# Cosmic_Pi_V2.net
KiCad netlist of a schematic drawn in EAGLE
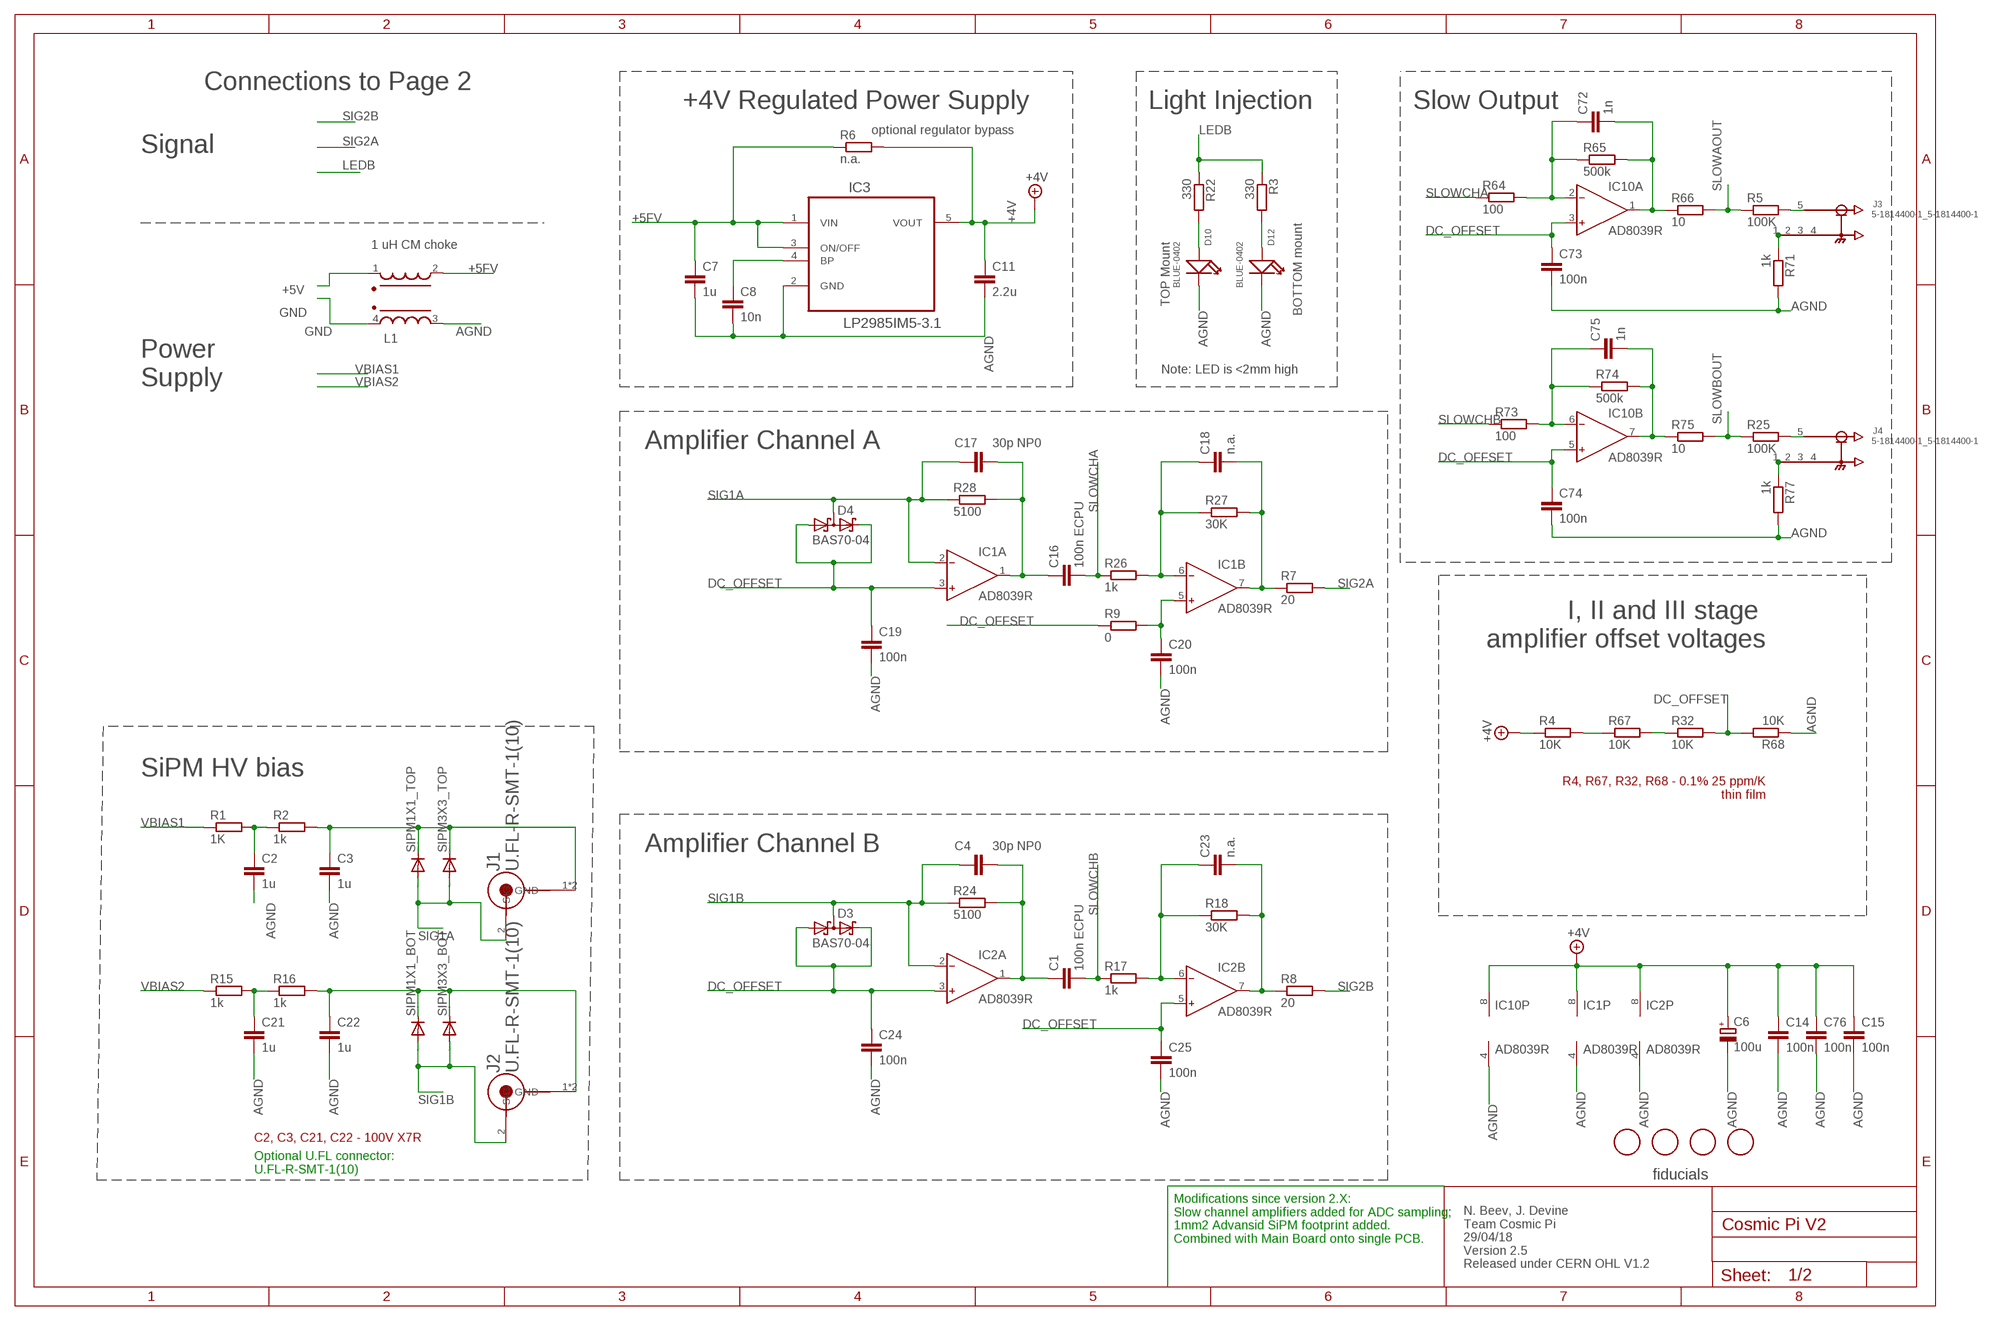
[diagram p0: schematic, sheet 1]
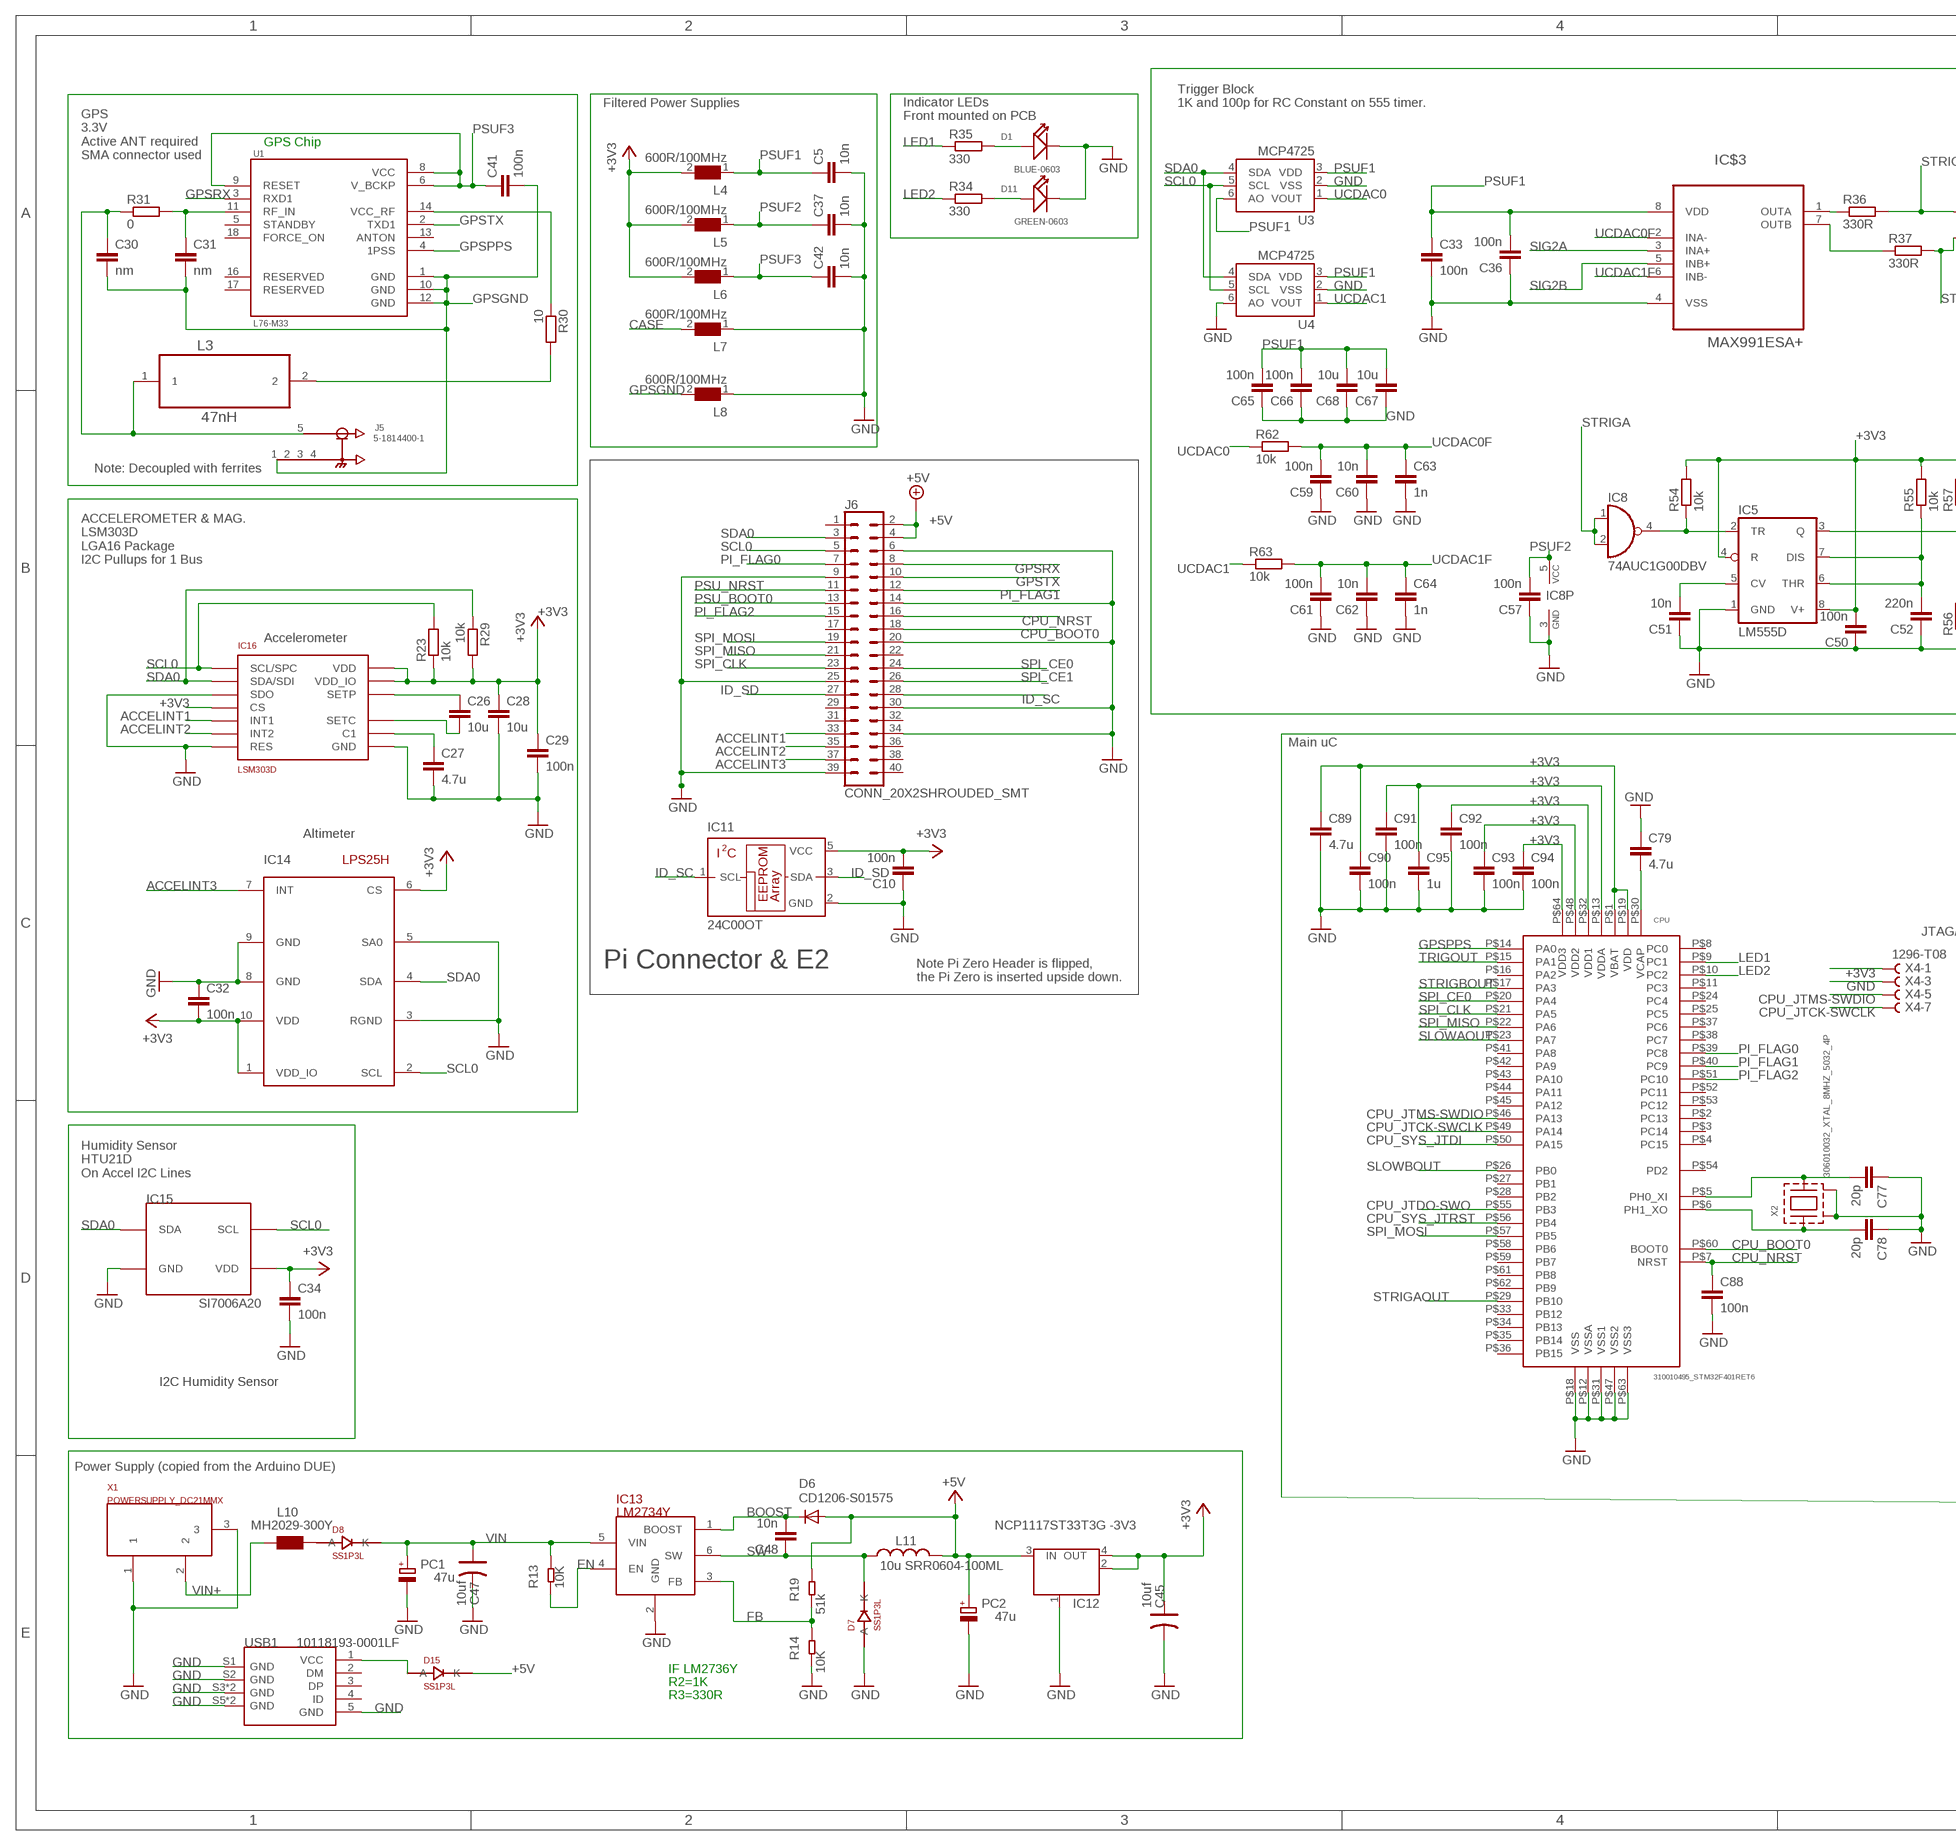
[diagram p1: schematic, sheet 2, part 1 of 2]
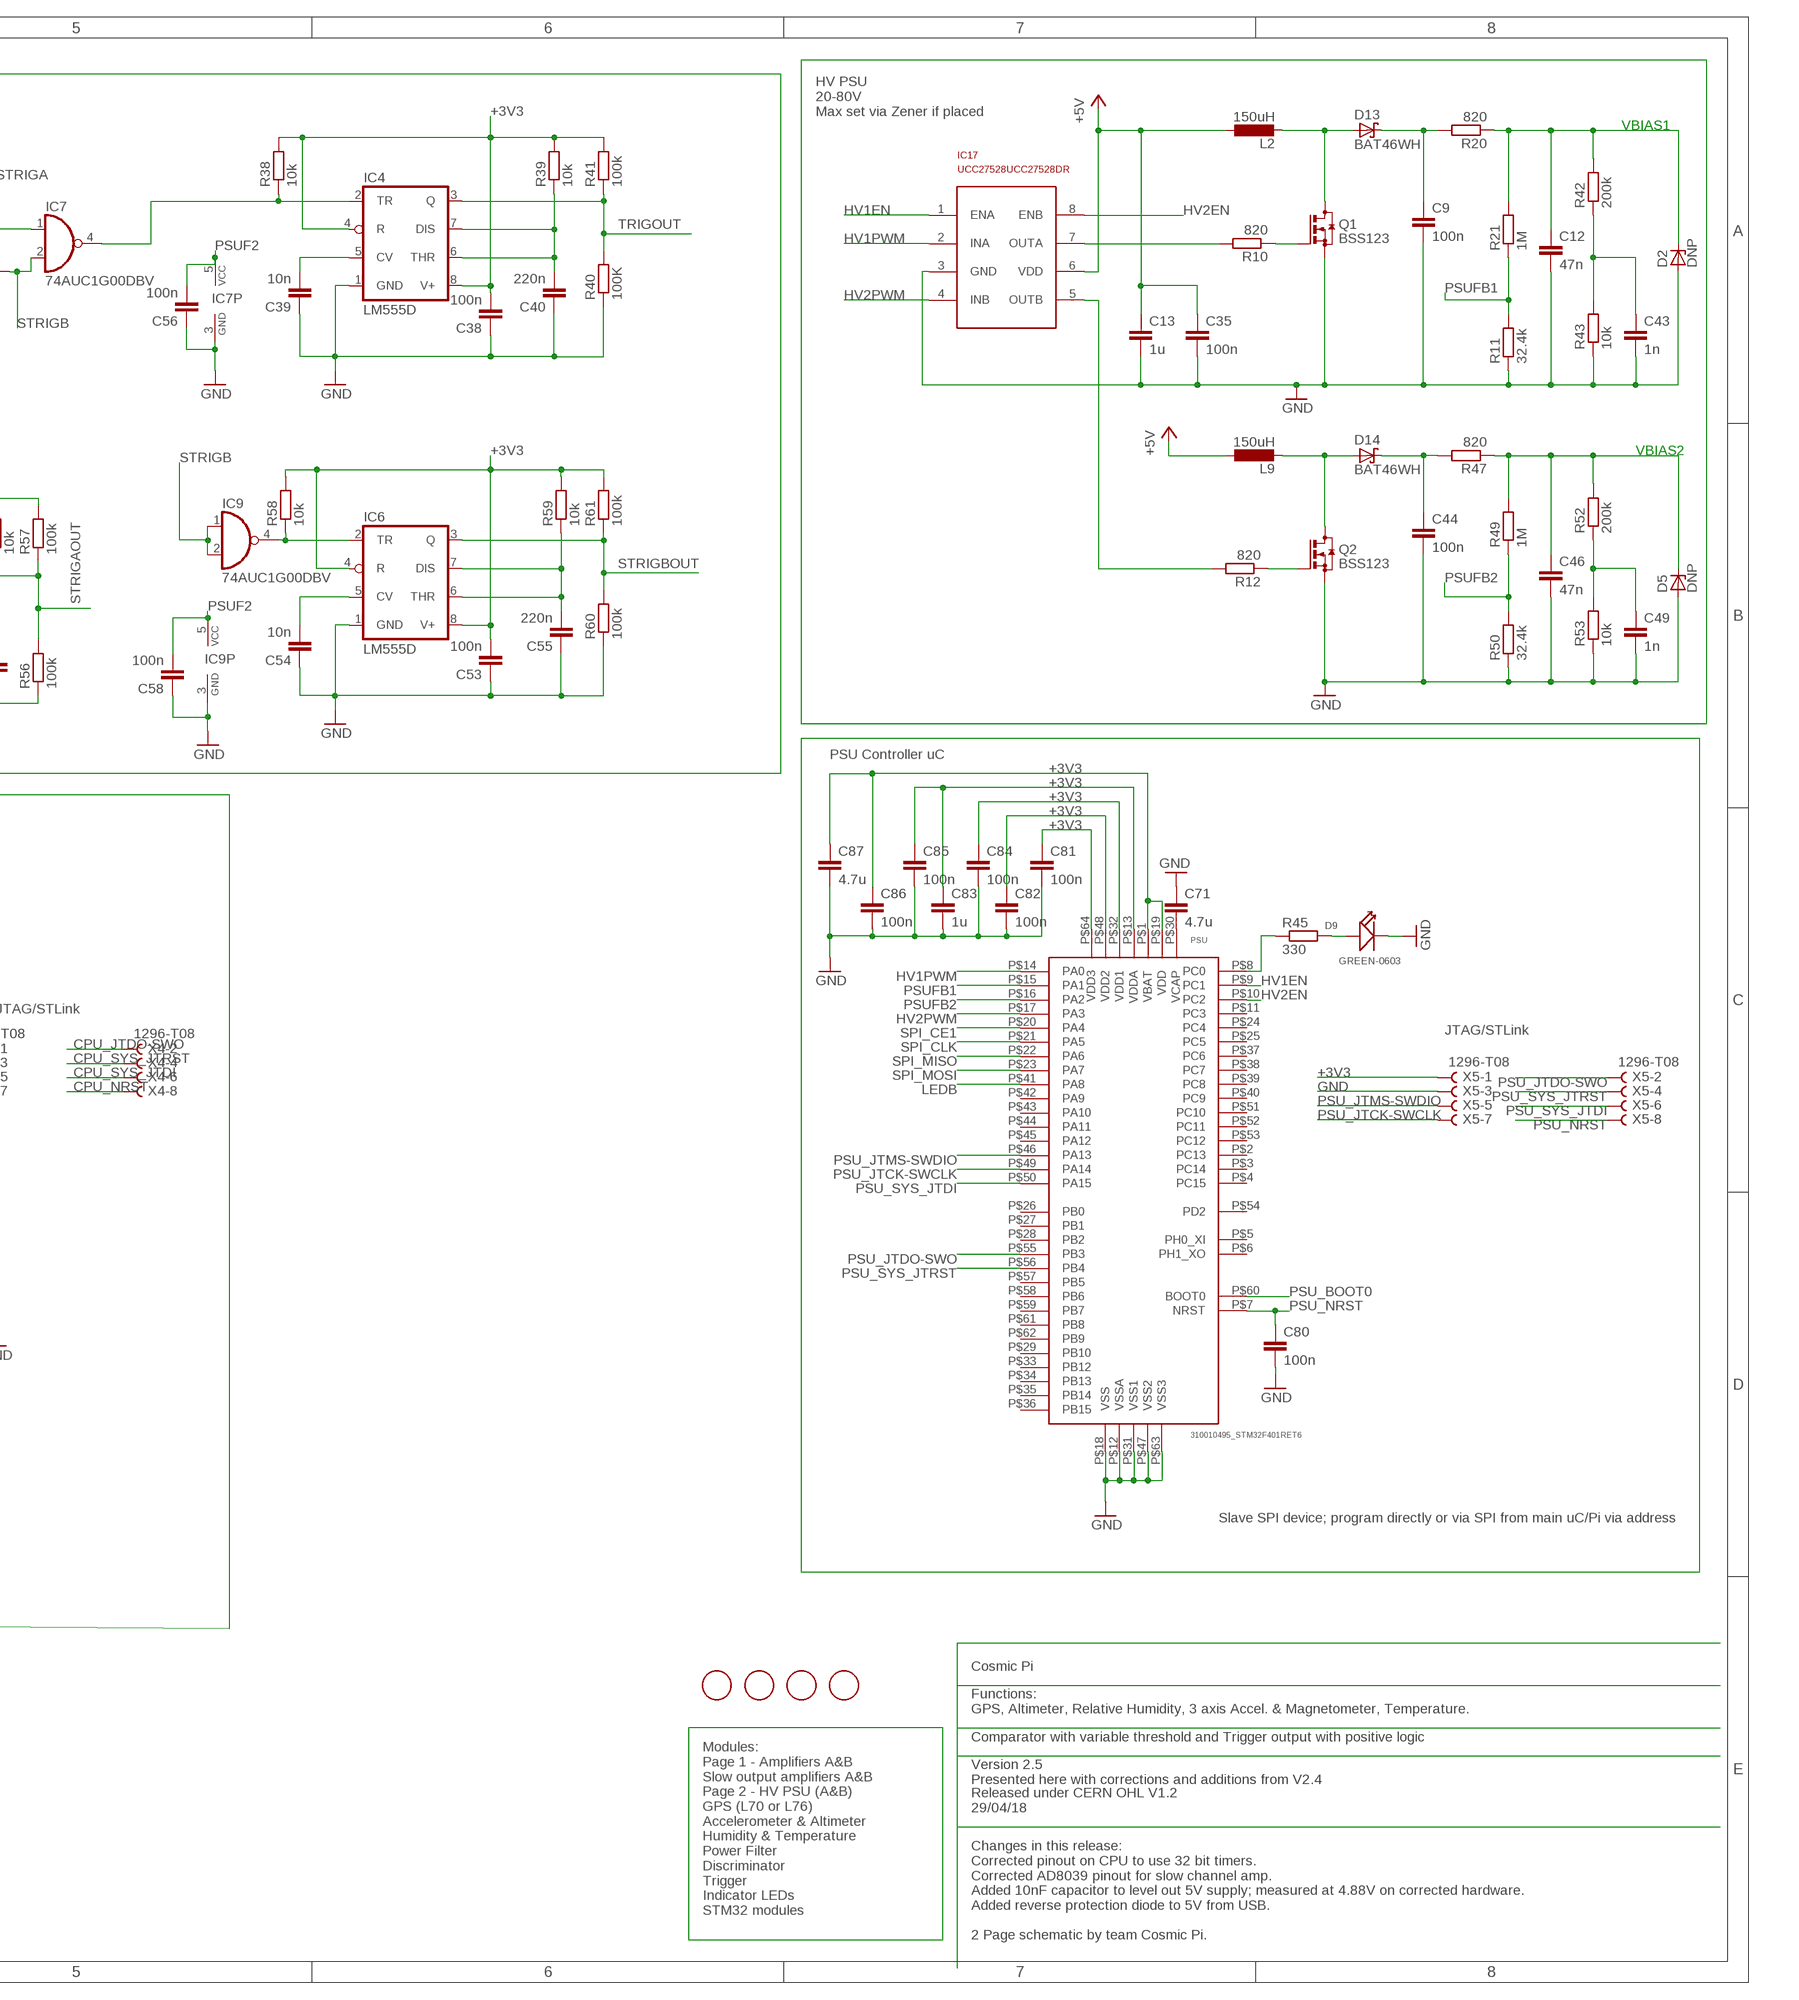
[diagram p2: schematic, sheet 2, part 2 of 2]

(export (version "E")
  (design (tool "Eeschema 10.0.6"))
  (components
    (comp (ref "C5")
      (value "10n")
      (footprint "eagle-import:C0603")
      (libsource (lib "eagle-import") (part "resistor_348_C-EUC0603"))
    )
    (comp (ref "C9")
      (value "100n")
      (footprint "eagle-import:C0603")
      (libsource (lib "eagle-import") (part "rcl_334_C-EUC0603"))
    )
    (comp (ref "C10")
      (value "100n")
      (footprint "eagle-import:C0603")
      (libsource (lib "eagle-import") (part "resistor_348_C-EUC0603"))
    )
    (comp (ref "C12")
      (value "47n")
      (footprint "eagle-import:C0603")
      (libsource (lib "eagle-import") (part "rcl_334_C-EUC0603"))
    )
    (comp (ref "C13")
      (value "1u")
      (footprint "eagle-import:C0603")
      (libsource (lib "eagle-import") (part "resistor_348_C-EUC0603"))
    )
    (comp (ref "C26")
      (value "10u")
      (footprint "eagle-import:C0603")
      (libsource (lib "eagle-import") (part "resistor_348_C-EUC0603"))
    )
    (comp (ref "C27")
      (value "4.7u")
      (footprint "eagle-import:C0603")
      (libsource (lib "eagle-import") (part "resistor_348_C-EUC0603"))
    )
    (comp (ref "C28")
      (value "10u")
      (footprint "eagle-import:C0603")
      (libsource (lib "eagle-import") (part "resistor_348_C-EUC0603"))
    )
    (comp (ref "C29")
      (value "100n")
      (footprint "eagle-import:C0603")
      (libsource (lib "eagle-import") (part "resistor_348_C-EUC0603"))
    )
    (comp (ref "C30")
      (value "nm")
      (footprint "eagle-import:C0603")
      (libsource (lib "eagle-import") (part "resistor_348_C-EUC0603"))
    )
    (comp (ref "C31")
      (value "nm")
      (footprint "eagle-import:C0603")
      (libsource (lib "eagle-import") (part "resistor_348_C-EUC0603"))
    )
    (comp (ref "C32")
      (value "100n")
      (footprint "eagle-import:C0603")
      (libsource (lib "eagle-import") (part "resistor_348_C-EUC0603"))
    )
    (comp (ref "C33")
      (value "100n")
      (footprint "eagle-import:C0603")
      (libsource (lib "eagle-import") (part "resistor_348_C-EUC0603"))
    )
    (comp (ref "C34")
      (value "100n")
      (footprint "eagle-import:C0603")
      (libsource (lib "eagle-import") (part "resistor_348_C-EUC0603"))
    )
    (comp (ref "C35")
      (value "100n")
      (footprint "eagle-import:C0603")
      (libsource (lib "eagle-import") (part "resistor_348_C-EUC0603"))
    )
    (comp (ref "C36")
      (value "100n")
      (footprint "eagle-import:C0603")
      (libsource (lib "eagle-import") (part "resistor_348_C-EUC0603"))
    )
    (comp (ref "C37")
      (value "10n")
      (footprint "eagle-import:C0603")
      (libsource (lib "eagle-import") (part "resistor_348_C-EUC0603"))
    )
    (comp (ref "C38")
      (value "100n")
      (footprint "eagle-import:C0603")
      (libsource (lib "eagle-import") (part "resistor_348_C-EUC0603"))
    )
    (comp (ref "C39")
      (value "10n")
      (footprint "eagle-import:C0603")
      (libsource (lib "eagle-import") (part "resistor_348_C-EUC0603"))
    )
    (comp (ref "C40")
      (value "220n")
      (footprint "eagle-import:C0603")
      (libsource (lib "eagle-import") (part "resistor_348_C-EUC0603"))
    )
    (comp (ref "C41")
      (value "100n")
      (footprint "eagle-import:C0603")
      (libsource (lib "eagle-import") (part "resistor_348_C-EUC0603"))
    )
    (comp (ref "C42")
      (value "10n")
      (footprint "eagle-import:C0603")
      (libsource (lib "eagle-import") (part "resistor_348_C-EUC0603"))
    )
    (comp (ref "C43")
      (value "1n")
      (footprint "eagle-import:C0603")
      (libsource (lib "eagle-import") (part "rcl_334_C-EUC0603"))
    )
    (comp (ref "C44")
      (value "100n")
      (footprint "eagle-import:C0603")
      (libsource (lib "eagle-import") (part "rcl_334_C-EUC0603"))
    )
    (comp (ref "C45")
      (value "10uf")
      (footprint "eagle-import:AVX-A")
      (fields (field (name "MPN") "TAJA106K016RNJ"))
      (libsource (lib "eagle-import") (part "TANTALUM-SMD-10UF-16V-10%(AVX-A)"))
    )
    (comp (ref "C46")
      (value "47n")
      (footprint "eagle-import:C0603")
      (libsource (lib "eagle-import") (part "rcl_334_C-EUC0603"))
    )
    (comp (ref "C47")
      (value "10uf")
      (footprint "eagle-import:AVX-A")
      (fields (field (name "MPN") "TAJA106K016RNJ"))
      (libsource (lib "eagle-import") (part "TANTALUM-SMD-10UF-16V-10%(AVX-A)"))
    )
    (comp (ref "C48")
      (value "10n")
      (footprint "eagle-import:C0603")
      (libsource (lib "eagle-import") (part "resistor_348_C-EUC0603"))
    )
    (comp (ref "C49")
      (value "1n")
      (footprint "eagle-import:C0603")
      (libsource (lib "eagle-import") (part "rcl_334_C-EUC0603"))
    )
    (comp (ref "C50")
      (value "100n")
      (footprint "eagle-import:C0603")
      (libsource (lib "eagle-import") (part "resistor_348_C-EUC0603"))
    )
    (comp (ref "C51")
      (value "10n")
      (footprint "eagle-import:C0603")
      (libsource (lib "eagle-import") (part "resistor_348_C-EUC0603"))
    )
    (comp (ref "C52")
      (value "220n")
      (footprint "eagle-import:C0603")
      (libsource (lib "eagle-import") (part "resistor_348_C-EUC0603"))
    )
    (comp (ref "C53")
      (value "100n")
      (footprint "eagle-import:C0603")
      (libsource (lib "eagle-import") (part "resistor_348_C-EUC0603"))
    )
    (comp (ref "C54")
      (value "10n")
      (footprint "eagle-import:C0603")
      (libsource (lib "eagle-import") (part "resistor_348_C-EUC0603"))
    )
    (comp (ref "C55")
      (value "220n")
      (footprint "eagle-import:C0603")
      (libsource (lib "eagle-import") (part "resistor_348_C-EUC0603"))
    )
    (comp (ref "C56")
      (value "100n")
      (footprint "eagle-import:C0603")
      (libsource (lib "eagle-import") (part "resistor_348_C-EUC0603"))
    )
    (comp (ref "C57")
      (value "100n")
      (footprint "eagle-import:C0603")
      (libsource (lib "eagle-import") (part "resistor_348_C-EUC0603"))
    )
    (comp (ref "C58")
      (value "100n")
      (footprint "eagle-import:C0603")
      (libsource (lib "eagle-import") (part "resistor_348_C-EUC0603"))
    )
    (comp (ref "C59")
      (value "100n")
      (footprint "eagle-import:C0603")
      (libsource (lib "eagle-import") (part "resistor_348_C-EUC0603"))
    )
    (comp (ref "C60")
      (value "10n")
      (footprint "eagle-import:C0603")
      (libsource (lib "eagle-import") (part "resistor_348_C-EUC0603"))
    )
    (comp (ref "C61")
      (value "100n")
      (footprint "eagle-import:C0603")
      (libsource (lib "eagle-import") (part "resistor_348_C-EUC0603"))
    )
    (comp (ref "C62")
      (value "10n")
      (footprint "eagle-import:C0603")
      (libsource (lib "eagle-import") (part "resistor_348_C-EUC0603"))
    )
    (comp (ref "C63")
      (value "1n")
      (footprint "eagle-import:C0603")
      (libsource (lib "eagle-import") (part "rcl_334_C-EUC0603"))
    )
    (comp (ref "C64")
      (value "1n")
      (footprint "eagle-import:C0603")
      (libsource (lib "eagle-import") (part "rcl_334_C-EUC0603"))
    )
    (comp (ref "C65")
      (value "100n")
      (footprint "eagle-import:C0603")
      (libsource (lib "eagle-import") (part "resistor_348_C-EUC0603"))
    )
    (comp (ref "C66")
      (value "100n")
      (footprint "eagle-import:C0603")
      (libsource (lib "eagle-import") (part "resistor_348_C-EUC0603"))
    )
    (comp (ref "C67")
      (value "10u")
      (footprint "eagle-import:C0603")
      (libsource (lib "eagle-import") (part "resistor_348_C-EUC0603"))
    )
    (comp (ref "C68")
      (value "10u")
      (footprint "eagle-import:C0603")
      (libsource (lib "eagle-import") (part "resistor_348_C-EUC0603"))
    )
    (comp (ref "C71")
      (value "4.7u")
      (footprint "eagle-import:C0603")
      (libsource (lib "eagle-import") (part "resistor_348_C-EUC0603"))
    )
    (comp (ref "C77")
      (value "20p")
      (footprint "eagle-import:C0603")
      (libsource (lib "eagle-import") (part "rcl_334_C-EUC0603"))
    )
    (comp (ref "C78")
      (value "20p")
      (footprint "eagle-import:C0603")
      (libsource (lib "eagle-import") (part "rcl_334_C-EUC0603"))
    )
    (comp (ref "C79")
      (value "4.7u")
      (footprint "eagle-import:C0603")
      (libsource (lib "eagle-import") (part "resistor_348_C-EUC0603"))
    )
    (comp (ref "C80")
      (value "100n")
      (footprint "eagle-import:C0603")
      (libsource (lib "eagle-import") (part "resistor_348_C-EUC0603"))
    )
    (comp (ref "C81")
      (value "100n")
      (footprint "eagle-import:C0603")
      (libsource (lib "eagle-import") (part "resistor_348_C-EUC0603"))
    )
    (comp (ref "C82")
      (value "100n")
      (footprint "eagle-import:C0603")
      (libsource (lib "eagle-import") (part "resistor_348_C-EUC0603"))
    )
    (comp (ref "C83")
      (value "1u")
      (footprint "eagle-import:C0603")
      (libsource (lib "eagle-import") (part "resistor_348_C-EUC0603"))
    )
    (comp (ref "C84")
      (value "100n")
      (footprint "eagle-import:C0603")
      (libsource (lib "eagle-import") (part "resistor_348_C-EUC0603"))
    )
    (comp (ref "C85")
      (value "100n")
      (footprint "eagle-import:C0603")
      (libsource (lib "eagle-import") (part "resistor_348_C-EUC0603"))
    )
    (comp (ref "C86")
      (value "100n")
      (footprint "eagle-import:C0603")
      (libsource (lib "eagle-import") (part "resistor_348_C-EUC0603"))
    )
    (comp (ref "C87")
      (value "4.7u")
      (footprint "eagle-import:C0603")
      (libsource (lib "eagle-import") (part "resistor_348_C-EUC0603"))
    )
    (comp (ref "C88")
      (value "100n")
      (footprint "eagle-import:C0603")
      (libsource (lib "eagle-import") (part "resistor_348_C-EUC0603"))
    )
    (comp (ref "C89")
      (value "4.7u")
      (footprint "eagle-import:C0603")
      (libsource (lib "eagle-import") (part "resistor_348_C-EUC0603"))
    )
    (comp (ref "C90")
      (value "100n")
      (footprint "eagle-import:C0603")
      (libsource (lib "eagle-import") (part "resistor_348_C-EUC0603"))
    )
    (comp (ref "C91")
      (value "100n")
      (footprint "eagle-import:C0603")
      (libsource (lib "eagle-import") (part "resistor_348_C-EUC0603"))
    )
    (comp (ref "C92")
      (value "100n")
      (footprint "eagle-import:C0603")
      (libsource (lib "eagle-import") (part "resistor_348_C-EUC0603"))
    )
    (comp (ref "C93")
      (value "100n")
      (footprint "eagle-import:C0603")
      (libsource (lib "eagle-import") (part "resistor_348_C-EUC0603"))
    )
    (comp (ref "C94")
      (value "100n")
      (footprint "eagle-import:C0603")
      (libsource (lib "eagle-import") (part "resistor_348_C-EUC0603"))
    )
    (comp (ref "C95")
      (value "1u")
      (footprint "eagle-import:C0603")
      (libsource (lib "eagle-import") (part "resistor_348_C-EUC0603"))
    )
    (comp (ref "CPU")
      (value "310010495_STM32F401RET6")
      (footprint "eagle-import:LQFP64")
      (libsource (lib "eagle-import") (part "310010495_STM32F401RET6"))
    )
    (comp (ref "D1")
      (value "BLUE-0603")
      (footprint "eagle-import:LED-0603")
      (fields (field (name "MPN") "19-217-BHC-ZL1M2RY-3T"))
      (libsource (lib "eagle-import") (part "SMD-LED-CLEAR-BLUE(0603)"))
    )
    (comp (ref "D2")
      (value "DNP")
      (footprint "eagle-import:SOT23")
      (libsource (lib "eagle-import") (part "ZENER-DIODESOT23"))
    )
    (comp (ref "D5")
      (value "DNP")
      (footprint "eagle-import:SOT23")
      (libsource (lib "eagle-import") (part "ZENER-DIODESOT23"))
    )
    (comp (ref "D6")
      (value "CD1206-S01575")
      (footprint "eagle-import:MINIMELF")
      (libsource (lib "eagle-import") (part "DIODE-MINIMELF"))
    )
    (comp (ref "D7")
      (value "SS1P3L")
      (footprint "eagle-import:DO220AAL")
      (libsource (lib "eagle-import") (part "SS1P3L"))
    )
    (comp (ref "D8")
      (value "SS1P3L")
      (footprint "eagle-import:DO220AAL")
      (libsource (lib "eagle-import") (part "SS1P3L"))
    )
    (comp (ref "D9")
      (value "GREEN-0603")
      (footprint "eagle-import:LED-0603")
      (fields (field (name "MPN") "19-217-G7C-AN1P2-3T"))
      (libsource (lib "eagle-import") (part "SMD-LED-CLEAR-GREEN(0603)"))
    )
    (comp (ref "D11")
      (value "GREEN-0603")
      (footprint "eagle-import:LED-0603")
      (fields (field (name "MPN") "19-217-G7C-AN1P2-3T"))
      (libsource (lib "eagle-import") (part "SMD-LED-CLEAR-GREEN(0603)"))
    )
    (comp (ref "D13")
      (value "BAT46WH")
      (footprint "eagle-import:SOD123F")
      (libsource (lib "eagle-import") (part "BAT46WH"))
    )
    (comp (ref "D14")
      (value "BAT46WH")
      (footprint "eagle-import:SOD123F")
      (libsource (lib "eagle-import") (part "BAT46WH"))
    )
    (comp (ref "D15")
      (value "SS1P3L")
      (footprint "eagle-import:DO220AAL")
      (libsource (lib "eagle-import") (part "SS1P3L"))
    )
    (comp (ref "IC$3")
      (value "MAX991ESA+")
      (footprint "eagle-import:SOIC-8")
      (libsource (lib "eagle-import") (part "MAX991ESA+"))
    )
    (comp (ref "IC4")
      (value "LM555D")
      (footprint "eagle-import:SO08")
      (libsource (lib "eagle-import") (part "555DLM"))
    )
    (comp (ref "IC5")
      (value "LM555D")
      (footprint "eagle-import:SO08")
      (libsource (lib "eagle-import") (part "555DLM"))
    )
    (comp (ref "IC6")
      (value "LM555D")
      (footprint "eagle-import:SO08")
      (libsource (lib "eagle-import") (part "555DLM"))
    )
    (comp (ref "IC7")
      (value "74AUC1G00DBV")
      (footprint "eagle-import:SOT23-5")
      (libsource (lib "eagle-import") (part "741G00DBVAUC"))
    )
    (comp (ref "IC8")
      (value "74AUC1G00DBV")
      (footprint "eagle-import:SOT23-5")
      (libsource (lib "eagle-import") (part "741G00DBVAUC"))
    )
    (comp (ref "IC9")
      (value "74AUC1G00DBV")
      (footprint "eagle-import:SOT23-5")
      (libsource (lib "eagle-import") (part "741G00DBVAUC"))
    )
    (comp (ref "IC11")
      (value "24C00OT")
      (footprint "eagle-import:SOT23-5L")
      (fields (field (name "MF") "MICROCHIP") (field (name "MPN") "24C00T-I/OT"))
      (libsource (lib "eagle-import") (part "24C0OT0"))
    )
    (comp (ref "IC12")
      (value "NCP1117ST33T3G -3V3")
      (footprint "eagle-import:SOT223")
      (libsource (lib "eagle-import") (part "MC33269ST-3.3T3"))
    )
    (comp (ref "IC13")
      (value "LM2734Y")
      (footprint "eagle-import:SOT23-6")
      (libsource (lib "eagle-import") (part "LM2736Y"))
    )
    (comp (ref "IC14")
      (value "LPS25H")
      (footprint "eagle-import:LPS25H")
      (libsource (lib "eagle-import") (part "LPS25H"))
    )
    (comp (ref "IC15")
      (value "SI7006A20")
      (footprint "eagle-import:3X3DFN")
      (libsource (lib "eagle-import") (part "SI7006A20"))
    )
    (comp (ref "IC16")
      (value "LSM303D")
      (footprint "eagle-import:LGA16L")
      (libsource (lib "eagle-import") (part "LSM303D"))
    )
    (comp (ref "IC17")
      (value "UCC27528UCC27528DR")
      (footprint "eagle-import:ANALOG-DEVICES_SO8")
      (libsource (lib "eagle-import") (part "UCC27528UCC27528DR"))
    )
    (comp (ref "J5")
      (value "5-1814400-1")
      (footprint "eagle-import:TE_5-1814400-1")
      (libsource (lib "eagle-import") (part "5-1814400-1_5-1814400-1"))
    )
    (comp (ref "J6")
      (value "CONN_20X2SHROUDED_SMT")
      (footprint "eagle-import:2X20_SHROUDED_SMT")
      (libsource (lib "eagle-import") (part "CONN_20X2SHROUDED_SMT"))
    )
    (comp (ref "L2")
      (value "150uH")
      (footprint "eagle-import:L1812")
      (libsource (lib "eagle-import") (part "L-EUL1812"))
    )
    (comp (ref "L3")
      (value "47nH")
      (footprint "eagle-import:INDC1608X90N")
      (libsource (lib "eagle-import") (part "B82496C3470J"))
    )
    (comp (ref "L4")
      (value "600R/100MHz")
      (footprint "eagle-import:1206")
      (fields (field (name "MPN") "74279218"))
      (libsource (lib "eagle-import") (part "WE-CBF_1206-74279218"))
    )
    (comp (ref "L5")
      (value "600R/100MHz")
      (footprint "eagle-import:1206")
      (fields (field (name "MPN") "74279218"))
      (libsource (lib "eagle-import") (part "WE-CBF_1206-74279218"))
    )
    (comp (ref "L6")
      (value "600R/100MHz")
      (footprint "eagle-import:1206")
      (fields (field (name "MPN") "74279218"))
      (libsource (lib "eagle-import") (part "WE-CBF_1206-74279218"))
    )
    (comp (ref "L7")
      (value "600R/100MHz")
      (footprint "eagle-import:1206")
      (fields (field (name "MPN") "74279218"))
      (libsource (lib "eagle-import") (part "WE-CBF_1206-74279218"))
    )
    (comp (ref "L8")
      (value "600R/100MHz")
      (footprint "eagle-import:1206")
      (fields (field (name "MPN") "74279218"))
      (libsource (lib "eagle-import") (part "WE-CBF_1206-74279218"))
    )
    (comp (ref "L9")
      (value "150uH")
      (footprint "eagle-import:L1812")
      (libsource (lib "eagle-import") (part "L-EUL1812"))
    )
    (comp (ref "L10")
      (value "MH2029-300Y")
      (footprint "eagle-import:0805")
      (libsource (lib "eagle-import") (part "wuerth-elektronik_WE-CBF_0805"))
    )
    (comp (ref "L11")
      (value "10u SRR0604-100ML")
      (footprint "eagle-import:SRR0604")
      (libsource (lib "eagle-import") (part "L-USSRR0604"))
    )
    (comp (ref "PC1")
      (value "47u")
      (footprint "eagle-import:PANASONIC_D")
      (libsource (lib "eagle-import") (part "CPOL-EUD"))
    )
    (comp (ref "PC2")
      (value "47u")
      (footprint "eagle-import:PANASONIC_D")
      (libsource (lib "eagle-import") (part "CPOL-EUD"))
    )
    (comp (ref "PSU")
      (value "310010495_STM32F401RET6")
      (footprint "eagle-import:LQFP64")
      (libsource (lib "eagle-import") (part "310010495_STM32F401RET6"))
    )
    (comp (ref "Q1")
      (value "BSS123")
      (footprint "eagle-import:SOT23")
      (libsource (lib "eagle-import") (part "BSS123"))
    )
    (comp (ref "Q2")
      (value "BSS123")
      (footprint "eagle-import:SOT23")
      (libsource (lib "eagle-import") (part "BSS123"))
    )
    (comp (ref "R10")
      (value "820")
      (footprint "eagle-import:R0603")
      (libsource (lib "eagle-import") (part "resistor_348_R-EU_R0603"))
    )
    (comp (ref "R11")
      (value "32.4k")
      (footprint "eagle-import:R0603")
      (libsource (lib "eagle-import") (part "resistor_348_R-EU_R0603"))
    )
    (comp (ref "R12")
      (value "820")
      (footprint "eagle-import:R0603")
      (libsource (lib "eagle-import") (part "resistor_348_R-EU_R0603"))
    )
    (comp (ref "R13")
      (value "10K")
      (footprint "eagle-import:R0603")
      (fields (field (name "MPN") "RC0603FR-0710KL"))
      (libsource (lib "eagle-import") (part "SMD-RES-10K-1%-1/10W(0603)"))
    )
    (comp (ref "R14")
      (value "10K")
      (footprint "eagle-import:R0603")
      (fields (field (name "MPN") "RC0603FR-0710KL"))
      (libsource (lib "eagle-import") (part "SMD-RES-10K-1%-1/10W(0603)"))
    )
    (comp (ref "R19")
      (value "51k")
      (footprint "eagle-import:R0603")
      (fields (field (name "MPN") "RC0603JR-0751KL"))
      (libsource (lib "eagle-import") (part "SMD-RES-51K-5%-1/10W(0603)"))
    )
    (comp (ref "R20")
      (value "820")
      (footprint "eagle-import:R0603")
      (libsource (lib "eagle-import") (part "resistor_348_R-EU_R0603"))
    )
    (comp (ref "R21")
      (value "1M")
      (footprint "eagle-import:R0603")
      (libsource (lib "eagle-import") (part "resistor_348_R-EU_R0603"))
    )
    (comp (ref "R23")
      (value "10k")
      (footprint "eagle-import:R0603")
      (libsource (lib "eagle-import") (part "resistor_348_R-EU_R0603"))
    )
    (comp (ref "R29")
      (value "10k")
      (footprint "eagle-import:R0603")
      (libsource (lib "eagle-import") (part "resistor_348_R-EU_R0603"))
    )
    (comp (ref "R30")
      (value "10")
      (footprint "eagle-import:R0603")
      (libsource (lib "eagle-import") (part "resistor_348_R-EU_R0603"))
    )
    (comp (ref "R31")
      (value "0")
      (footprint "eagle-import:R0603")
      (libsource (lib "eagle-import") (part "resistor_348_R-EU_R0603"))
    )
    (comp (ref "R34")
      (value "330")
      (footprint "eagle-import:R0603")
      (libsource (lib "eagle-import") (part "resistor_348_R-EU_R0603"))
    )
    (comp (ref "R35")
      (value "330")
      (footprint "eagle-import:R0603")
      (libsource (lib "eagle-import") (part "resistor_348_R-EU_R0603"))
    )
    (comp (ref "R36")
      (value "330R")
      (footprint "eagle-import:R0603")
      (libsource (lib "eagle-import") (part "resistor_348_R-EU_R0603"))
    )
    (comp (ref "R37")
      (value "330R")
      (footprint "eagle-import:R0603")
      (libsource (lib "eagle-import") (part "resistor_348_R-EU_R0603"))
    )
    (comp (ref "R38")
      (value "10k")
      (footprint "eagle-import:R0603")
      (libsource (lib "eagle-import") (part "resistor_348_R-EU_R0603"))
    )
    (comp (ref "R39")
      (value "10k")
      (footprint "eagle-import:R0603")
      (libsource (lib "eagle-import") (part "resistor_348_R-EU_R0603"))
    )
    (comp (ref "R40")
      (value "100K")
      (footprint "eagle-import:R0603")
      (libsource (lib "eagle-import") (part "resistor_348_R-EU_R0603"))
    )
    (comp (ref "R41")
      (value "100k")
      (footprint "eagle-import:R0603")
      (libsource (lib "eagle-import") (part "resistor_348_R-EU_R0603"))
    )
    (comp (ref "R42")
      (value "200k")
      (footprint "eagle-import:R0603")
      (libsource (lib "eagle-import") (part "resistor_348_R-EU_R0603"))
    )
    (comp (ref "R43")
      (value "10k")
      (footprint "eagle-import:R0603")
      (libsource (lib "eagle-import") (part "resistor_348_R-EU_R0603"))
    )
    (comp (ref "R45")
      (value "330")
      (footprint "eagle-import:R0603")
      (libsource (lib "eagle-import") (part "resistor_348_R-EU_R0603"))
    )
    (comp (ref "R47")
      (value "820")
      (footprint "eagle-import:R0603")
      (libsource (lib "eagle-import") (part "resistor_348_R-EU_R0603"))
    )
    (comp (ref "R49")
      (value "1M")
      (footprint "eagle-import:R0603")
      (libsource (lib "eagle-import") (part "resistor_348_R-EU_R0603"))
    )
    (comp (ref "R50")
      (value "32.4k")
      (footprint "eagle-import:R0603")
      (libsource (lib "eagle-import") (part "resistor_348_R-EU_R0603"))
    )
    (comp (ref "R52")
      (value "200k")
      (footprint "eagle-import:R0603")
      (libsource (lib "eagle-import") (part "resistor_348_R-EU_R0603"))
    )
    (comp (ref "R53")
      (value "10k")
      (footprint "eagle-import:R0603")
      (libsource (lib "eagle-import") (part "resistor_348_R-EU_R0603"))
    )
    (comp (ref "R54")
      (value "10k")
      (footprint "eagle-import:R0603")
      (libsource (lib "eagle-import") (part "resistor_348_R-EU_R0603"))
    )
    (comp (ref "R55")
      (value "10k")
      (footprint "eagle-import:R0603")
      (libsource (lib "eagle-import") (part "resistor_348_R-EU_R0603"))
    )
    (comp (ref "R56")
      (value "100k")
      (footprint "eagle-import:R0603")
      (libsource (lib "eagle-import") (part "resistor_348_R-EU_R0603"))
    )
    (comp (ref "R57")
      (value "100k")
      (footprint "eagle-import:R0603")
      (libsource (lib "eagle-import") (part "resistor_348_R-EU_R0603"))
    )
    (comp (ref "R58")
      (value "10k")
      (footprint "eagle-import:R0603")
      (libsource (lib "eagle-import") (part "resistor_348_R-EU_R0603"))
    )
    (comp (ref "R59")
      (value "10k")
      (footprint "eagle-import:R0603")
      (libsource (lib "eagle-import") (part "resistor_348_R-EU_R0603"))
    )
    (comp (ref "R60")
      (value "100k")
      (footprint "eagle-import:R0603")
      (libsource (lib "eagle-import") (part "resistor_348_R-EU_R0603"))
    )
    (comp (ref "R61")
      (value "100k")
      (footprint "eagle-import:R0603")
      (libsource (lib "eagle-import") (part "resistor_348_R-EU_R0603"))
    )
    (comp (ref "R62")
      (value "10k")
      (footprint "eagle-import:R0603")
      (libsource (lib "eagle-import") (part "resistor_348_R-EU_R0603"))
    )
    (comp (ref "R63")
      (value "10k")
      (footprint "eagle-import:R0603")
      (libsource (lib "eagle-import") (part "resistor_348_R-EU_R0603"))
    )
    (comp (ref "U$1")
      (value "FIDUCIAL")
      (footprint "eagle-import:FIDUCIAL_1MM")
      (libsource (lib "eagle-import") (part "FIDUCIAL"))
    )
    (comp (ref "U$6")
      (value "FIDUCIAL")
      (footprint "eagle-import:FIDUCIAL_1MM")
      (libsource (lib "eagle-import") (part "FIDUCIAL"))
    )
    (comp (ref "U$7")
      (value "FIDUCIAL")
      (footprint "eagle-import:FIDUCIAL_1MM")
      (libsource (lib "eagle-import") (part "FIDUCIAL"))
    )
    (comp (ref "U$8")
      (value "FIDUCIAL")
      (footprint "eagle-import:FIDUCIAL_1MM")
      (libsource (lib "eagle-import") (part "FIDUCIAL"))
    )
    (comp (ref "U1")
      (value "L76-M33")
      (footprint "eagle-import:CAPCAV110P970X1010X250-18N")
      (libsource (lib "eagle-import") (part "L76-M33"))
    )
    (comp (ref "U3")
      (value "MCP4725")
      (footprint "eagle-import:SOT23-6")
      (libsource (lib "eagle-import") (part "MCP4725SOT-23"))
    )
    (comp (ref "U4")
      (value "MCP4725")
      (footprint "eagle-import:SOT23-6")
      (libsource (lib "eagle-import") (part "MCP4725SOT-23"))
    )
    (comp (ref "USB1")
      (value "10118193-0001LF")
      (footprint "eagle-import:MICRO-USB5+6P-SMD-0.65-B")
      (libsource (lib "eagle-import") (part "MICRO-USB-SMD-B-(10118193-0001LF)"))
    )
    (comp (ref "X1")
      (value "POWERSUPPLY_DC21MMX")
      (footprint "eagle-import:POWERSUPPLY_DC-21MM")
      (libsource (lib "eagle-import") (part "POWERSUPPLY_DC21MMX"))
    )
    (comp (ref "X2")
      (value "306010032_XTAL_8MHZ_5032_4P")
      (footprint "eagle-import:X5032_4P")
      (libsource (lib "eagle-import") (part "306010032_XTAL_8MHZ_5032_4P"))
    )
    (comp (ref "X4")
      (value "1296-T08")
      (footprint "eagle-import:1296-08")
      (libsource (lib "eagle-import") (part "1296-T08"))
    )
    (comp (ref "X5")
      (value "1296-T08")
      (footprint "eagle-import:1296-08")
      (libsource (lib "eagle-import") (part "1296-T08"))
    )
    (comp (ref "C1")
      (value "100n ECPU")
      (footprint "eagle-import:C0805")
      (libsource (lib "eagle-import") (part "C-EUC0805"))
    )
    (comp (ref "C2")
      (value "1u")
      (footprint "eagle-import:C1206")
      (libsource (lib "eagle-import") (part "C-EUC1206"))
    )
    (comp (ref "C3")
      (value "1u")
      (footprint "eagle-import:C1206")
      (libsource (lib "eagle-import") (part "C-EUC1206"))
    )
    (comp (ref "C4")
      (value "30p NP0")
      (footprint "eagle-import:C0603")
      (libsource (lib "eagle-import") (part "C-EUC0603"))
    )
    (comp (ref "C6")
      (value "100u")
      (footprint "eagle-import:C_6032-28R")
      (libsource (lib "eagle-import") (part "CPOL-EUC/6032-28R"))
    )
    (comp (ref "C7")
      (value "1u")
      (footprint "eagle-import:C0603")
      (libsource (lib "eagle-import") (part "resistor_C-EUC0603"))
    )
    (comp (ref "C8")
      (value "10n")
      (footprint "eagle-import:C0603")
      (libsource (lib "eagle-import") (part "resistor_C-EUC0603"))
    )
    (comp (ref "C11")
      (value "2.2u")
      (footprint "eagle-import:C0603")
      (libsource (lib "eagle-import") (part "resistor_C-EUC0603"))
    )
    (comp (ref "C14")
      (value "100n")
      (footprint "eagle-import:C0603")
      (libsource (lib "eagle-import") (part "resistor_C-EUC0603"))
    )
    (comp (ref "C15")
      (value "100n")
      (footprint "eagle-import:C0603")
      (libsource (lib "eagle-import") (part "resistor_C-EUC0603"))
    )
    (comp (ref "C16")
      (value "100n ECPU")
      (footprint "eagle-import:C0805")
      (libsource (lib "eagle-import") (part "C-EUC0805"))
    )
    (comp (ref "C17")
      (value "30p NP0")
      (footprint "eagle-import:C0603")
      (libsource (lib "eagle-import") (part "C-EUC0603"))
    )
    (comp (ref "C18")
      (value "n.a.")
      (footprint "eagle-import:C0603")
      (libsource (lib "eagle-import") (part "C-EUC0603"))
    )
    (comp (ref "C19")
      (value "100n")
      (footprint "eagle-import:C0603")
      (libsource (lib "eagle-import") (part "resistor_C-EUC0603"))
    )
    (comp (ref "C20")
      (value "100n")
      (footprint "eagle-import:C0603")
      (libsource (lib "eagle-import") (part "resistor_C-EUC0603"))
    )
    (comp (ref "C21")
      (value "1u")
      (footprint "eagle-import:C1206")
      (libsource (lib "eagle-import") (part "C-EUC1206"))
    )
    (comp (ref "C22")
      (value "1u")
      (footprint "eagle-import:C1206")
      (libsource (lib "eagle-import") (part "C-EUC1206"))
    )
    (comp (ref "C23")
      (value "n.a.")
      (footprint "eagle-import:C0603")
      (libsource (lib "eagle-import") (part "C-EUC0603"))
    )
    (comp (ref "C24")
      (value "100n")
      (footprint "eagle-import:C0603")
      (libsource (lib "eagle-import") (part "resistor_C-EUC0603"))
    )
    (comp (ref "C25")
      (value "100n")
      (footprint "eagle-import:C0603")
      (libsource (lib "eagle-import") (part "resistor_C-EUC0603"))
    )
    (comp (ref "C72")
      (value "1n")
      (footprint "eagle-import:C0603")
      (libsource (lib "eagle-import") (part "C-EUC0603"))
    )
    (comp (ref "C73")
      (value "100n")
      (footprint "eagle-import:C0603")
      (libsource (lib "eagle-import") (part "resistor_C-EUC0603"))
    )
    (comp (ref "C74")
      (value "100n")
      (footprint "eagle-import:C0603")
      (libsource (lib "eagle-import") (part "resistor_C-EUC0603"))
    )
    (comp (ref "C75")
      (value "1n")
      (footprint "eagle-import:C0603")
      (libsource (lib "eagle-import") (part "C-EUC0603"))
    )
    (comp (ref "C76")
      (value "100n")
      (footprint "eagle-import:C0603")
      (libsource (lib "eagle-import") (part "resistor_C-EUC0603"))
    )
    (comp (ref "D3")
      (value "BAS70-04")
      (footprint "eagle-import:SOT23")
      (libsource (lib "eagle-import") (part "BAS70-04"))
    )
    (comp (ref "D4")
      (value "BAS70-04")
      (footprint "eagle-import:SOT23")
      (libsource (lib "eagle-import") (part "BAS70-04"))
    )
    (comp (ref "D10")
      (value "BLUE-0402")
      (footprint "eagle-import:LED-0402")
      (fields (field (name "MPN") "BL-HB337A-AV-TRB") (field (name "POSITION") "TOP Mount"))
      (libsource (lib "eagle-import") (part "SMD-LED-CLEAR-BLUE(0402)"))
    )
    (comp (ref "D12")
      (value "BLUE-0402")
      (footprint "eagle-import:LED-0402")
      (fields (field (name "MPN") "BL-HB337A-AV-TRB") (field (name "POSITION") "BOTTOM mount"))
      (libsource (lib "eagle-import") (part "SMD-LED-CLEAR-BLUE(0402)"))
    )
    (comp (ref "IC1")
      (value "AD8039R")
      (footprint "eagle-import:SO8")
      (fields (field (name "MF") "ALTERA CORPORATION") (field (name "MPN") "AD8033ARZ"))
      (libsource (lib "eagle-import") (part "AD8039R"))
    )
    (comp (ref "IC2")
      (value "AD8039R")
      (footprint "eagle-import:SO8")
      (fields (field (name "MF") "ALTERA CORPORATION") (field (name "MPN") "AD8033ARZ"))
      (libsource (lib "eagle-import") (part "AD8039R"))
    )
    (comp (ref "IC3")
      (value "LP2985IM5-3.1")
      (footprint "eagle-import:SOT95P284X120-5N")
      (libsource (lib "eagle-import") (part "LP2985IM5-3.1"))
    )
    (comp (ref "IC10")
      (value "AD8039R")
      (footprint "eagle-import:SO8")
      (fields (field (name "MF") "ALTERA CORPORATION") (field (name "MPN") "AD8033ARZ"))
      (libsource (lib "eagle-import") (part "AD8039R"))
    )
    (comp (ref "J1")
      (value "U.FL-R-SMT-1(10)")
      (footprint "eagle-import:HRS_U.FL-R-SMT-1(10)")
      (fields (field (name "MF") "Hirose"))
      (libsource (lib "eagle-import") (part "U.FL-R-SMT-1(10)"))
    )
    (comp (ref "J2")
      (value "U.FL-R-SMT-1(10)")
      (footprint "eagle-import:HRS_U.FL-R-SMT-1(10)")
      (fields (field (name "MF") "Hirose"))
      (libsource (lib "eagle-import") (part "U.FL-R-SMT-1(10)"))
    )
    (comp (ref "J3")
      (value "5-1814400-1_5-1814400-1")
      (footprint "eagle-import:5-1814400-1_TE_5-1814400-1")
      (libsource (lib "eagle-import") (part "5-1814400-1_5-1814400-1"))
    )
    (comp (ref "J4")
      (value "5-1814400-1_5-1814400-1")
      (footprint "eagle-import:5-1814400-1_TE_5-1814400-1")
      (libsource (lib "eagle-import") (part "5-1814400-1_5-1814400-1"))
    )
    (comp (ref "L1")
      (value "1 uH CM choke")
      (footprint "eagle-import:WE-CNSW_1812")
      (libsource (lib "eagle-import") (part "WE-CNSW_1812_744235601"))
    )
    (comp (ref "R1")
      (value "1K")
      (footprint "eagle-import:R1206")
      (libsource (lib "eagle-import") (part "R-EU_R1206"))
    )
    (comp (ref "R2")
      (value "1k")
      (footprint "eagle-import:R1206")
      (libsource (lib "eagle-import") (part "R-EU_R1206"))
    )
    (comp (ref "R3")
      (value "330")
      (footprint "eagle-import:R0603")
      (libsource (lib "eagle-import") (part "resistor_R-EU_R0603"))
    )
    (comp (ref "R4")
      (value "10K")
      (footprint "eagle-import:R0805")
      (libsource (lib "eagle-import") (part "R-EU_R0805"))
    )
    (comp (ref "R5")
      (value "100K")
      (footprint "eagle-import:R0603")
      (libsource (lib "eagle-import") (part "R-EU_R0603"))
    )
    (comp (ref "R6")
      (value "n.a.")
      (footprint "eagle-import:R0603")
      (libsource (lib "eagle-import") (part "R-EU_R0603"))
    )
    (comp (ref "R7")
      (value "20")
      (footprint "eagle-import:R0603")
      (libsource (lib "eagle-import") (part "R-EU_R0603"))
    )
    (comp (ref "R8")
      (value "20")
      (footprint "eagle-import:R0603")
      (libsource (lib "eagle-import") (part "R-EU_R0603"))
    )
    (comp (ref "R9")
      (value "0")
      (footprint "eagle-import:R1206")
      (libsource (lib "eagle-import") (part "R-EU_R1206"))
    )
    (comp (ref "R15")
      (value "1k")
      (footprint "eagle-import:R1206")
      (libsource (lib "eagle-import") (part "R-EU_R1206"))
    )
    (comp (ref "R16")
      (value "1k")
      (footprint "eagle-import:R1206")
      (libsource (lib "eagle-import") (part "R-EU_R1206"))
    )
    (comp (ref "R17")
      (value "1k")
      (footprint "eagle-import:R0603")
      (libsource (lib "eagle-import") (part "R-EU_R0603"))
    )
    (comp (ref "R18")
      (value "30K")
      (footprint "eagle-import:R0603")
      (libsource (lib "eagle-import") (part "R-EU_R0603"))
    )
    (comp (ref "R22")
      (value "330")
      (footprint "eagle-import:R0603")
      (libsource (lib "eagle-import") (part "resistor_R-EU_R0603"))
    )
    (comp (ref "R24")
      (value "5100")
      (footprint "eagle-import:R0603")
      (libsource (lib "eagle-import") (part "R-EU_R0603"))
    )
    (comp (ref "R25")
      (value "100K")
      (footprint "eagle-import:R0603")
      (libsource (lib "eagle-import") (part "R-EU_R0603"))
    )
    (comp (ref "R26")
      (value "1k")
      (footprint "eagle-import:R0603")
      (libsource (lib "eagle-import") (part "R-EU_R0603"))
    )
    (comp (ref "R27")
      (value "30K")
      (footprint "eagle-import:R0603")
      (libsource (lib "eagle-import") (part "R-EU_R0603"))
    )
    (comp (ref "R28")
      (value "5100")
      (footprint "eagle-import:R0603")
      (libsource (lib "eagle-import") (part "R-EU_R0603"))
    )
    (comp (ref "R32")
      (value "10K")
      (footprint "eagle-import:R0805")
      (libsource (lib "eagle-import") (part "R-EU_R0805"))
    )
    (comp (ref "R64")
      (value "100")
      (footprint "eagle-import:R0603")
      (libsource (lib "eagle-import") (part "R-EU_R0603"))
    )
    (comp (ref "R65")
      (value "500k")
      (footprint "eagle-import:R0603")
      (libsource (lib "eagle-import") (part "R-EU_R0603"))
    )
    (comp (ref "R66")
      (value "10")
      (footprint "eagle-import:R0603")
      (libsource (lib "eagle-import") (part "R-EU_R0603"))
    )
    (comp (ref "R67")
      (value "10K")
      (footprint "eagle-import:R0805")
      (libsource (lib "eagle-import") (part "R-EU_R0805"))
    )
    (comp (ref "R68")
      (value "10K")
      (footprint "eagle-import:R0805")
      (libsource (lib "eagle-import") (part "R-EU_R0805"))
    )
    (comp (ref "R71")
      (value "1k")
      (footprint "eagle-import:R0603")
      (libsource (lib "eagle-import") (part "R-EU_R0603"))
    )
    (comp (ref "R73")
      (value "100")
      (footprint "eagle-import:R0603")
      (libsource (lib "eagle-import") (part "R-EU_R0603"))
    )
    (comp (ref "R74")
      (value "500k")
      (footprint "eagle-import:R0603")
      (libsource (lib "eagle-import") (part "R-EU_R0603"))
    )
    (comp (ref "R75")
      (value "10")
      (footprint "eagle-import:R0603")
      (libsource (lib "eagle-import") (part "R-EU_R0603"))
    )
    (comp (ref "R77")
      (value "1k")
      (footprint "eagle-import:R0603")
      (libsource (lib "eagle-import") (part "R-EU_R0603"))
    )
    (comp (ref "SIPM1X1_BOT")
      (value "DIODE_DIODE-ADVANSID1X1")
      (footprint "eagle-import:DIODE_ASD-NUV1S-P")
      (libsource (lib "eagle-import") (part "DIODE_DIODE-ADVANSID1X1"))
    )
    (comp (ref "SIPM1X1_TOP")
      (value "DIODE_DIODE-ADVANSID1X1")
      (footprint "eagle-import:DIODE_ASD-NUV1S-P")
      (libsource (lib "eagle-import") (part "DIODE_DIODE-ADVANSID1X1"))
    )
    (comp (ref "SIPM3X3_BOT")
      (value "DIODE_DIODE-ADVANSID3X3")
      (footprint "eagle-import:DIODE_ASD-NUV3S-P")
      (libsource (lib "eagle-import") (part "DIODE_DIODE-ADVANSID3X3"))
    )
    (comp (ref "SIPM3X3_TOP")
      (value "DIODE_DIODE-ADVANSID3X3")
      (footprint "eagle-import:DIODE_ASD-NUV3S-P")
      (libsource (lib "eagle-import") (part "DIODE_DIODE-ADVANSID3X3"))
    )
    (comp (ref "U$2")
      (value "FIDUCIAL")
      (footprint "eagle-import:FIDUCIAL_1MM")
      (libsource (lib "eagle-import") (part "FIDUCIAL"))
    )
    (comp (ref "U$3")
      (value "FIDUCIAL")
      (footprint "eagle-import:FIDUCIAL_1MM")
      (libsource (lib "eagle-import") (part "FIDUCIAL"))
    )
    (comp (ref "U$4")
      (value "FIDUCIAL")
      (footprint "eagle-import:FIDUCIAL_1MM")
      (libsource (lib "eagle-import") (part "FIDUCIAL"))
    )
    (comp (ref "U$5")
      (value "FIDUCIAL")
      (footprint "eagle-import:FIDUCIAL_1MM")
      (libsource (lib "eagle-import") (part "FIDUCIAL"))
    )
  )
  (nets
    (net (code "1") (name "+3V3") (class "Default")
      (node (ref "C10") (pin "2") (pinfunction "2_2") (pintype "passive"))
      (node (ref "C28") (pin "1") (pinfunction "1_1") (pintype "passive"))
      (node (ref "C29") (pin "1") (pinfunction "1_1") (pintype "passive"))
      (node (ref "C32") (pin "2") (pinfunction "2_2") (pintype "passive"))
      (node (ref "C34") (pin "1") (pinfunction "1_1") (pintype "passive"))
      (node (ref "C38") (pin "2") (pinfunction "2_2") (pintype "passive"))
      (node (ref "C45") (pin "+") (pinfunction "+_+") (pintype "passive"))
      (node (ref "C50") (pin "2") (pinfunction "2_2") (pintype "passive"))
      (node (ref "C53") (pin "2") (pinfunction "2_2") (pintype "passive"))
      (node (ref "C81") (pin "1") (pinfunction "1_1") (pintype "passive"))
      (node (ref "C82") (pin "1") (pinfunction "1_1") (pintype "passive"))
      (node (ref "C83") (pin "1") (pinfunction "1_1") (pintype "passive"))
      (node (ref "C84") (pin "1") (pinfunction "1_1") (pintype "passive"))
      (node (ref "C85") (pin "1") (pinfunction "1_1") (pintype "passive"))
      (node (ref "C86") (pin "1") (pinfunction "1_1") (pintype "passive"))
      (node (ref "C87") (pin "1") (pinfunction "1_1") (pintype "passive"))
      (node (ref "C89") (pin "1") (pinfunction "1_1") (pintype "passive"))
      (node (ref "C90") (pin "1") (pinfunction "1_1") (pintype "passive"))
      (node (ref "C91") (pin "1") (pinfunction "1_1") (pintype "passive"))
      (node (ref "C92") (pin "1") (pinfunction "1_1") (pintype "passive"))
      (node (ref "C93") (pin "1") (pinfunction "1_1") (pintype "passive"))
      (node (ref "C94") (pin "1") (pinfunction "1_1") (pintype "passive"))
      (node (ref "C95") (pin "1") (pinfunction "1_1") (pintype "passive"))
      (node (ref "CPU") (pin "P$1") (pinfunction "VBAT_P$1") (pintype "power_in"))
      (node (ref "CPU") (pin "P$13") (pinfunction "VDDA_P$13") (pintype "power_in"))
      (node (ref "CPU") (pin "P$19") (pinfunction "VDD_P$19") (pintype "power_in"))
      (node (ref "CPU") (pin "P$32") (pinfunction "VDD1_P$32") (pintype "power_in"))
      (node (ref "CPU") (pin "P$48") (pinfunction "VDD2_P$48") (pintype "power_in"))
      (node (ref "CPU") (pin "P$64") (pinfunction "VDD3_P$64") (pintype "power_in"))
      (node (ref "IC11") (pin "5") (pinfunction "VCC_5") (pintype "power_in"))
      (node (ref "IC12") (pin "2") (pinfunction "OUT_2") (pintype "passive"))
      (node (ref "IC12") (pin "4") (pinfunction "OUT_4") (pintype "passive"))
      (node (ref "IC14") (pin "1") (pinfunction "VDD_IO_1") (pintype "power_in"))
      (node (ref "IC14") (pin "10") (pinfunction "VDD_10") (pintype "power_in"))
      (node (ref "IC14") (pin "6") (pinfunction "CS_6") (pintype "bidirectional"))
      (node (ref "IC15") (pin "P$5") (pinfunction "VDD_P$5") (pintype "bidirectional"))
      (node (ref "IC16") (pin "P$1") (pinfunction "VDD_IO_P$1") (pintype "power_in"))
      (node (ref "IC16") (pin "P$14") (pinfunction "VDD_P$14") (pintype "power_in"))
      (node (ref "IC16") (pin "P$8") (pinfunction "CS_P$8") (pintype "bidirectional"))
      (node (ref "IC4") (pin "4") (pinfunction "R_4") (pintype "input"))
      (node (ref "IC4") (pin "8") (pinfunction "V+_8") (pintype "power_in"))
      (node (ref "IC5") (pin "4") (pinfunction "R_4") (pintype "input"))
      (node (ref "IC5") (pin "8") (pinfunction "V+_8") (pintype "power_in"))
      (node (ref "IC6") (pin "4") (pinfunction "R_4") (pintype "input"))
      (node (ref "IC6") (pin "8") (pinfunction "V+_8") (pintype "power_in"))
      (node (ref "L4") (pin "2") (pinfunction "2_2") (pintype "passive"))
      (node (ref "L5") (pin "2") (pinfunction "2_2") (pintype "passive"))
      (node (ref "L6") (pin "2") (pinfunction "2_2") (pintype "passive"))
      (node (ref "PSU") (pin "P$1") (pinfunction "VBAT_P$1") (pintype "power_in"))
      (node (ref "PSU") (pin "P$13") (pinfunction "VDDA_P$13") (pintype "power_in"))
      (node (ref "PSU") (pin "P$19") (pinfunction "VDD_P$19") (pintype "power_in"))
      (node (ref "PSU") (pin "P$32") (pinfunction "VDD1_P$32") (pintype "power_in"))
      (node (ref "PSU") (pin "P$48") (pinfunction "VDD2_P$48") (pintype "power_in"))
      (node (ref "PSU") (pin "P$64") (pinfunction "VDD3_P$64") (pintype "power_in"))
      (node (ref "R23") (pin "1") (pinfunction "1_1") (pintype "passive"))
      (node (ref "R29") (pin "2") (pinfunction "2_2") (pintype "passive"))
      (node (ref "R38") (pin "2") (pinfunction "2_2") (pintype "passive"))
      (node (ref "R39") (pin "2") (pinfunction "2_2") (pintype "passive"))
      (node (ref "R41") (pin "2") (pinfunction "2_2") (pintype "passive"))
      (node (ref "R54") (pin "2") (pinfunction "2_2") (pintype "passive"))
      (node (ref "R55") (pin "2") (pinfunction "2_2") (pintype "passive"))
      (node (ref "R57") (pin "2") (pinfunction "2_2") (pintype "passive"))
      (node (ref "R58") (pin "2") (pinfunction "2_2") (pintype "passive"))
      (node (ref "R59") (pin "2") (pinfunction "2_2") (pintype "passive"))
      (node (ref "R61") (pin "2") (pinfunction "2_2") (pintype "passive"))
      (node (ref "X4") (pin "1") (pinfunction "B_1") (pintype "passive"))
      (node (ref "X5") (pin "1") (pinfunction "B_1") (pintype "passive"))
    )
    (net (code "2") (name "+4V") (class "Default")
      (node (ref "C11") (pin "1") (pinfunction "1_1") (pintype "passive"))
      (node (ref "C14") (pin "1") (pinfunction "1_1") (pintype "passive"))
      (node (ref "C15") (pin "1") (pinfunction "1_1") (pintype "passive"))
      (node (ref "C6") (pin "+") (pinfunction "+_+") (pintype "passive"))
      (node (ref "C76") (pin "1") (pinfunction "1_1") (pintype "passive"))
      (node (ref "IC1") (pin "8") (pinfunction "V+_8") (pintype "power_in"))
      (node (ref "IC10") (pin "8") (pinfunction "V+_8") (pintype "power_in"))
      (node (ref "IC2") (pin "8") (pinfunction "V+_8") (pintype "power_in"))
      (node (ref "IC3") (pin "5") (pinfunction "VOUT_5") (pintype "output"))
      (node (ref "R4") (pin "1") (pinfunction "1_1") (pintype "passive"))
      (node (ref "R6") (pin "2") (pinfunction "2_2") (pintype "passive"))
    )
    (net (code "3") (name "+5FV") (class "Default")
      (node (ref "C7") (pin "1") (pinfunction "1_1") (pintype "passive"))
      (node (ref "IC3") (pin "1") (pinfunction "VIN_1") (pintype "power_in"))
      (node (ref "IC3") (pin "3") (pinfunction "ON/OFF_3") (pintype "input"))
      (node (ref "L1") (pin "2") (pinfunction "3_2") (pintype "passive"))
      (node (ref "R6") (pin "1") (pinfunction "1_1") (pintype "passive"))
    )
    (net (code "4") (name "+5V") (class "Default")
      (node (ref "C13") (pin "1") (pinfunction "1_1") (pintype "passive"))
      (node (ref "C35") (pin "1") (pinfunction "1_1") (pintype "passive"))
      (node (ref "D15") (pin "P$1") (pinfunction "K_P$1") (pintype "bidirectional"))
      (node (ref "D6") (pin "A") (pinfunction "A_A") (pintype "passive"))
      (node (ref "IC12") (pin "3") (pinfunction "IN_3") (pintype "input"))
      (node (ref "IC17") (pin "6") (pinfunction "VDD_6") (pintype "bidirectional"))
      (node (ref "J6") (pin "2") (pinfunction "2_2") (pintype "passive"))
      (node (ref "J6") (pin "4") (pinfunction "4_4") (pintype "passive"))
      (node (ref "L1") (pin "1") (pinfunction "4_1") (pintype "passive"))
      (node (ref "L11") (pin "P$2") (pinfunction "2_P$2") (pintype "passive"))
      (node (ref "L2") (pin "1") (pinfunction "1_1") (pintype "passive"))
      (node (ref "L9") (pin "1") (pinfunction "1_1") (pintype "passive"))
      (node (ref "PC2") (pin "+") (pinfunction "+_+") (pintype "passive"))
      (node (ref "R19") (pin "1") (pinfunction "1_1") (pintype "passive"))
    )
    (net (code "5") (name "ACCELINT1") (class "Default")
      (node (ref "IC16") (pin "P$11") (pinfunction "INT1_P$11") (pintype "bidirectional"))
      (node (ref "J6") (pin "33") (pinfunction "33_33") (pintype "passive"))
    )
    (net (code "6") (name "ACCELINT2") (class "Default")
      (node (ref "IC16") (pin "P$9") (pinfunction "INT2_P$9") (pintype "bidirectional"))
      (node (ref "J6") (pin "35") (pinfunction "35_35") (pintype "passive"))
    )
    (net (code "7") (name "ACCELINT3") (class "Default")
      (node (ref "IC14") (pin "7") (pinfunction "INT_7") (pintype "bidirectional"))
      (node (ref "J6") (pin "37") (pinfunction "37_37") (pintype "passive"))
    )
    (net (code "8") (name "AGND") (class "Default")
      (node (ref "C11") (pin "2") (pinfunction "2_2") (pintype "passive"))
      (node (ref "C14") (pin "2") (pinfunction "2_2") (pintype "passive"))
      (node (ref "C15") (pin "2") (pinfunction "2_2") (pintype "passive"))
      (node (ref "C19") (pin "2") (pinfunction "2_2") (pintype "passive"))
      (node (ref "C2") (pin "2") (pinfunction "2_2") (pintype "passive"))
      (node (ref "C20") (pin "2") (pinfunction "2_2") (pintype "passive"))
      (node (ref "C21") (pin "2") (pinfunction "2_2") (pintype "passive"))
      (node (ref "C22") (pin "2") (pinfunction "2_2") (pintype "passive"))
      (node (ref "C24") (pin "2") (pinfunction "2_2") (pintype "passive"))
      (node (ref "C25") (pin "2") (pinfunction "2_2") (pintype "passive"))
      (node (ref "C3") (pin "2") (pinfunction "2_2") (pintype "passive"))
      (node (ref "C6") (pin "-") (pinfunction "-_-") (pintype "passive"))
      (node (ref "C7") (pin "2") (pinfunction "2_2") (pintype "passive"))
      (node (ref "C73") (pin "2") (pinfunction "2_2") (pintype "passive"))
      (node (ref "C74") (pin "2") (pinfunction "2_2") (pintype "passive"))
      (node (ref "C76") (pin "2") (pinfunction "2_2") (pintype "passive"))
      (node (ref "C8") (pin "2") (pinfunction "2_2") (pintype "passive"))
      (node (ref "D10") (pin "-") (pinfunction "-_-") (pintype "passive"))
      (node (ref "D12") (pin "-") (pinfunction "-_-") (pintype "passive"))
      (node (ref "IC1") (pin "4") (pinfunction "V-_4") (pintype "power_in"))
      (node (ref "IC10") (pin "4") (pinfunction "V-_4") (pintype "power_in"))
      (node (ref "IC2") (pin "4") (pinfunction "V-_4") (pintype "power_in"))
      (node (ref "IC3") (pin "2") (pinfunction "GND_2") (pintype "passive"))
      (node (ref "L1") (pin "3") (pinfunction "2_3") (pintype "passive"))
      (node (ref "R68") (pin "1") (pinfunction "1_1") (pintype "passive"))
      (node (ref "R71") (pin "2") (pinfunction "2_2") (pintype "passive"))
      (node (ref "R77") (pin "2") (pinfunction "2_2") (pintype "passive"))
    )
    (net (code "9") (name "BOOST") (class "Default")
      (node (ref "C48") (pin "2") (pinfunction "2_2") (pintype "passive"))
      (node (ref "D6") (pin "C") (pinfunction "C_C") (pintype "passive"))
      (node (ref "IC13") (pin "1") (pinfunction "BOOST_1") (pintype "input"))
    )
    (net (code "10") (name "CASE") (class "Default")
      (node (ref "L7") (pin "2") (pinfunction "2_2") (pintype "passive"))
    )
    (net (code "11") (name "CPU_BOOT0") (class "Default")
      (node (ref "CPU") (pin "P$60") (pinfunction "BOOT0_P$60") (pintype "bidirectional"))
      (node (ref "J6") (pin "18") (pinfunction "18_18") (pintype "passive"))
    )
    (net (code "12") (name "CPU_JTCK-SWCLK") (class "Default")
      (node (ref "CPU") (pin "P$49") (pinfunction "PA14_P$49") (pintype "bidirectional"))
      (node (ref "X4") (pin "7") (pinfunction "B_7") (pintype "passive"))
    )
    (net (code "13") (name "CPU_JTDO-SWO") (class "Default")
      (node (ref "CPU") (pin "P$55") (pinfunction "PB3_P$55") (pintype "bidirectional"))
      (node (ref "X4") (pin "2") (pinfunction "B_2") (pintype "passive"))
    )
    (net (code "14") (name "CPU_JTMS-SWDIO") (class "Default")
      (node (ref "CPU") (pin "P$46") (pinfunction "PA13_P$46") (pintype "bidirectional"))
      (node (ref "X4") (pin "5") (pinfunction "B_5") (pintype "passive"))
    )
    (net (code "15") (name "CPU_NRST") (class "Default")
      (node (ref "C88") (pin "1") (pinfunction "1_1") (pintype "passive"))
      (node (ref "CPU") (pin "P$7") (pinfunction "NRST_P$7") (pintype "bidirectional"))
      (node (ref "J6") (pin "16") (pinfunction "16_16") (pintype "passive"))
      (node (ref "X4") (pin "8") (pinfunction "B_8") (pintype "passive"))
    )
    (net (code "16") (name "CPU_SYS_JTDI") (class "Default")
      (node (ref "CPU") (pin "P$50") (pinfunction "PA15_P$50") (pintype "bidirectional"))
      (node (ref "X4") (pin "6") (pinfunction "B_6") (pintype "passive"))
    )
    (net (code "17") (name "CPU_SYS_JTRST") (class "Default")
      (node (ref "CPU") (pin "P$56") (pinfunction "PB4_P$56") (pintype "bidirectional"))
      (node (ref "X4") (pin "4") (pinfunction "B_4") (pintype "passive"))
    )
    (net (code "18") (name "DC_OFFSET") (class "Default")
      (node (ref "C19") (pin "1") (pinfunction "1_1") (pintype "passive"))
      (node (ref "C24") (pin "1") (pinfunction "1_1") (pintype "passive"))
      (node (ref "C25") (pin "1") (pinfunction "1_1") (pintype "passive"))
      (node (ref "C73") (pin "1") (pinfunction "1_1") (pintype "passive"))
      (node (ref "C74") (pin "1") (pinfunction "1_1") (pintype "passive"))
      (node (ref "D3") (pin "1") (pinfunction "A1_1") (pintype "passive"))
      (node (ref "D3") (pin "2") (pinfunction "C2_2") (pintype "passive"))
      (node (ref "D4") (pin "1") (pinfunction "A1_1") (pintype "passive"))
      (node (ref "D4") (pin "2") (pinfunction "C2_2") (pintype "passive"))
      (node (ref "IC1") (pin "3") (pinfunction "IN+_3") (pintype "input"))
      (node (ref "IC10") (pin "3") (pinfunction "IN+_3") (pintype "input"))
      (node (ref "IC10") (pin "5") (pinfunction "IN+_5") (pintype "input"))
      (node (ref "IC2") (pin "3") (pinfunction "IN+_3") (pintype "input"))
      (node (ref "IC2") (pin "5") (pinfunction "IN+_5") (pintype "input"))
      (node (ref "R32") (pin "2") (pinfunction "2_2") (pintype "passive"))
      (node (ref "R68") (pin "2") (pinfunction "2_2") (pintype "passive"))
      (node (ref "R9") (pin "1") (pinfunction "1_1") (pintype "passive"))
    )
    (net (code "19") (name "EN") (class "Default")
      (node (ref "IC13") (pin "4") (pinfunction "EN_4") (pintype "input"))
      (node (ref "R13") (pin "2") (pinfunction "2_2") (pintype "passive"))
    )
    (net (code "20") (name "FB") (class "Default")
      (node (ref "IC13") (pin "3") (pinfunction "FB_3") (pintype "input"))
      (node (ref "R14") (pin "1") (pinfunction "1_1") (pintype "passive"))
      (node (ref "R19") (pin "2") (pinfunction "2_2") (pintype "passive"))
    )
    (net (code "21") (name "GND") (class "Default")
      (node (ref "C10") (pin "1") (pinfunction "1_1") (pintype "passive"))
      (node (ref "C12") (pin "2") (pinfunction "2_2") (pintype "passive"))
      (node (ref "C13") (pin "2") (pinfunction "2_2") (pintype "passive"))
      (node (ref "C27") (pin "2") (pinfunction "2_2") (pintype "passive"))
      (node (ref "C28") (pin "2") (pinfunction "2_2") (pintype "passive"))
      (node (ref "C29") (pin "2") (pinfunction "2_2") (pintype "passive"))
      (node (ref "C32") (pin "1") (pinfunction "1_1") (pintype "passive"))
      (node (ref "C33") (pin "2") (pinfunction "2_2") (pintype "passive"))
      (node (ref "C34") (pin "2") (pinfunction "2_2") (pintype "passive"))
      (node (ref "C35") (pin "2") (pinfunction "2_2") (pintype "passive"))
      (node (ref "C36") (pin "1") (pinfunction "1_1") (pintype "passive"))
      (node (ref "C37") (pin "2") (pinfunction "2_2") (pintype "passive"))
      (node (ref "C38") (pin "1") (pinfunction "1_1") (pintype "passive"))
      (node (ref "C39") (pin "1") (pinfunction "1_1") (pintype "passive"))
      (node (ref "C40") (pin "1") (pinfunction "1_1") (pintype "passive"))
      (node (ref "C42") (pin "2") (pinfunction "2_2") (pintype "passive"))
      (node (ref "C43") (pin "2") (pinfunction "2_2") (pintype "passive"))
      (node (ref "C44") (pin "2") (pinfunction "2_2") (pintype "passive"))
      (node (ref "C45") (pin "-") (pinfunction "-_-") (pintype "passive"))
      (node (ref "C46") (pin "2") (pinfunction "2_2") (pintype "passive"))
      (node (ref "C47") (pin "-") (pinfunction "-_-") (pintype "passive"))
      (node (ref "C49") (pin "2") (pinfunction "2_2") (pintype "passive"))
      (node (ref "C5") (pin "2") (pinfunction "2_2") (pintype "passive"))
      (node (ref "C50") (pin "1") (pinfunction "1_1") (pintype "passive"))
      (node (ref "C51") (pin "1") (pinfunction "1_1") (pintype "passive"))
      (node (ref "C52") (pin "1") (pinfunction "1_1") (pintype "passive"))
      (node (ref "C53") (pin "1") (pinfunction "1_1") (pintype "passive"))
      (node (ref "C54") (pin "1") (pinfunction "1_1") (pintype "passive"))
      (node (ref "C55") (pin "1") (pinfunction "1_1") (pintype "passive"))
      (node (ref "C56") (pin "1") (pinfunction "1_1") (pintype "passive"))
      (node (ref "C57") (pin "1") (pinfunction "1_1") (pintype "passive"))
      (node (ref "C58") (pin "1") (pinfunction "1_1") (pintype "passive"))
      (node (ref "C59") (pin "1") (pinfunction "1_1") (pintype "passive"))
      (node (ref "C60") (pin "1") (pinfunction "1_1") (pintype "passive"))
      (node (ref "C61") (pin "1") (pinfunction "1_1") (pintype "passive"))
      (node (ref "C62") (pin "1") (pinfunction "1_1") (pintype "passive"))
      (node (ref "C63") (pin "2") (pinfunction "2_2") (pintype "passive"))
      (node (ref "C64") (pin "2") (pinfunction "2_2") (pintype "passive"))
      (node (ref "C65") (pin "1") (pinfunction "1_1") (pintype "passive"))
      (node (ref "C66") (pin "1") (pinfunction "1_1") (pintype "passive"))
      (node (ref "C67") (pin "1") (pinfunction "1_1") (pintype "passive"))
      (node (ref "C68") (pin "1") (pinfunction "1_1") (pintype "passive"))
      (node (ref "C71") (pin "1") (pinfunction "1_1") (pintype "passive"))
      (node (ref "C77") (pin "1") (pinfunction "1_1") (pintype "passive"))
      (node (ref "C78") (pin "1") (pinfunction "1_1") (pintype "passive"))
      (node (ref "C79") (pin "1") (pinfunction "1_1") (pintype "passive"))
      (node (ref "C80") (pin "2") (pinfunction "2_2") (pintype "passive"))
      (node (ref "C81") (pin "2") (pinfunction "2_2") (pintype "passive"))
      (node (ref "C82") (pin "2") (pinfunction "2_2") (pintype "passive"))
      (node (ref "C83") (pin "2") (pinfunction "2_2") (pintype "passive"))
      (node (ref "C84") (pin "2") (pinfunction "2_2") (pintype "passive"))
      (node (ref "C85") (pin "2") (pinfunction "2_2") (pintype "passive"))
      (node (ref "C86") (pin "2") (pinfunction "2_2") (pintype "passive"))
      (node (ref "C87") (pin "2") (pinfunction "2_2") (pintype "passive"))
      (node (ref "C88") (pin "2") (pinfunction "2_2") (pintype "passive"))
      (node (ref "C89") (pin "2") (pinfunction "2_2") (pintype "passive"))
      (node (ref "C9") (pin "2") (pinfunction "2_2") (pintype "passive"))
      (node (ref "C90") (pin "2") (pinfunction "2_2") (pintype "passive"))
      (node (ref "C91") (pin "2") (pinfunction "2_2") (pintype "passive"))
      (node (ref "C92") (pin "2") (pinfunction "2_2") (pintype "passive"))
      (node (ref "C93") (pin "2") (pinfunction "2_2") (pintype "passive"))
      (node (ref "C94") (pin "2") (pinfunction "2_2") (pintype "passive"))
      (node (ref "C95") (pin "2") (pinfunction "2_2") (pintype "passive"))
      (node (ref "CPU") (pin "P$12") (pinfunction "VSSA_P$12") (pintype "power_in"))
      (node (ref "CPU") (pin "P$18") (pinfunction "VSS_P$18") (pintype "power_in"))
      (node (ref "CPU") (pin "P$31") (pinfunction "VSS1_P$31") (pintype "power_in"))
      (node (ref "CPU") (pin "P$47") (pinfunction "VSS2_P$47") (pintype "power_in"))
      (node (ref "CPU") (pin "P$63") (pinfunction "VSS3_P$63") (pintype "power_in"))
      (node (ref "D1") (pin "-") (pinfunction "-_-") (pintype "passive"))
      (node (ref "D11") (pin "-") (pinfunction "-_-") (pintype "passive"))
      (node (ref "D2") (pin "1") (pinfunction "A_1") (pintype "passive"))
      (node (ref "D5") (pin "1") (pinfunction "A_1") (pintype "passive"))
      (node (ref "D7") (pin "P$2") (pinfunction "A_P$2") (pintype "bidirectional"))
      (node (ref "D9") (pin "-") (pinfunction "-_-") (pintype "passive"))
      (node (ref "IC$3") (pin "4") (pinfunction "VSS_4") (pintype "power_in"))
      (node (ref "IC11") (pin "2") (pinfunction "GND_2") (pintype "power_in"))
      (node (ref "IC12") (pin "1") (pinfunction "GND/ADJ_1") (pintype "input"))
      (node (ref "IC13") (pin "2") (pinfunction "GND_2") (pintype "power_in"))
      (node (ref "IC14") (pin "3") (pinfunction "RGND_3") (pintype "bidirectional"))
      (node (ref "IC14") (pin "5") (pinfunction "SA0_5") (pintype "bidirectional"))
      (node (ref "IC14") (pin "8") (pinfunction "GND_8") (pintype "power_in"))
      (node (ref "IC14") (pin "9") (pinfunction "GND_9") (pintype "power_in"))
      (node (ref "IC15") (pin "P$2") (pinfunction "GND_P$2") (pintype "bidirectional"))
      (node (ref "IC16") (pin "P$10") (pinfunction "RES_P$10") (pintype "bidirectional"))
      (node (ref "IC16") (pin "P$12") (pinfunction "GND_P$12") (pintype "power_in"))
      (node (ref "IC16") (pin "P$13") (pinfunction "GND_P$13") (pintype "power_in"))
      (node (ref "IC16") (pin "P$16") (pinfunction "GND_P$16") (pintype "power_in"))
      (node (ref "IC16") (pin "P$5") (pinfunction "GND_P$5") (pintype "power_in"))
      (node (ref "IC16") (pin "P$7") (pinfunction "SDO_P$7") (pintype "bidirectional"))
      (node (ref "IC17") (pin "3") (pinfunction "GND_3") (pintype "bidirectional"))
      (node (ref "IC4") (pin "1") (pinfunction "GND_1") (pintype "power_in"))
      (node (ref "IC5") (pin "1") (pinfunction "GND_1") (pintype "power_in"))
      (node (ref "IC6") (pin "1") (pinfunction "GND_1") (pintype "power_in"))
      (node (ref "IC7") (pin "3") (pinfunction "GND_3") (pintype "power_in"))
      (node (ref "IC8") (pin "3") (pinfunction "GND_3") (pintype "power_in"))
      (node (ref "IC9") (pin "3") (pinfunction "GND_3") (pintype "power_in"))
      (node (ref "J6") (pin "14") (pinfunction "14_14") (pintype "passive"))
      (node (ref "J6") (pin "20") (pinfunction "20_20") (pintype "passive"))
      (node (ref "J6") (pin "25") (pinfunction "25_25") (pintype "passive"))
      (node (ref "J6") (pin "30") (pinfunction "30_30") (pintype "passive"))
      (node (ref "J6") (pin "34") (pinfunction "34_34") (pintype "passive"))
      (node (ref "J6") (pin "39") (pinfunction "39_39") (pintype "passive"))
      (node (ref "J6") (pin "6") (pinfunction "6_6") (pintype "passive"))
      (node (ref "J6") (pin "9") (pinfunction "9_9") (pintype "passive"))
      (node (ref "L1") (pin "4") (pinfunction "1_4") (pintype "passive"))
      (node (ref "L7") (pin "1") (pinfunction "1_1") (pintype "passive"))
      (node (ref "L8") (pin "1") (pinfunction "1_1") (pintype "passive"))
      (node (ref "PC1") (pin "-") (pinfunction "-_-") (pintype "passive"))
      (node (ref "PC2") (pin "-") (pinfunction "-_-") (pintype "passive"))
      (node (ref "PSU") (pin "P$12") (pinfunction "VSSA_P$12") (pintype "power_in"))
      (node (ref "PSU") (pin "P$18") (pinfunction "VSS_P$18") (pintype "power_in"))
      (node (ref "PSU") (pin "P$31") (pinfunction "VSS1_P$31") (pintype "power_in"))
      (node (ref "PSU") (pin "P$47") (pinfunction "VSS2_P$47") (pintype "power_in"))
      (node (ref "PSU") (pin "P$63") (pinfunction "VSS3_P$63") (pintype "power_in"))
      (node (ref "Q1") (pin "2") (pinfunction "S_2") (pintype "passive"))
      (node (ref "Q2") (pin "2") (pinfunction "S_2") (pintype "passive"))
      (node (ref "R11") (pin "1") (pinfunction "1_1") (pintype "passive"))
      (node (ref "R14") (pin "2") (pinfunction "2_2") (pintype "passive"))
      (node (ref "R40") (pin "1") (pinfunction "1_1") (pintype "passive"))
      (node (ref "R43") (pin "1") (pinfunction "1_1") (pintype "passive"))
      (node (ref "R50") (pin "1") (pinfunction "1_1") (pintype "passive"))
      (node (ref "R53") (pin "1") (pinfunction "1_1") (pintype "passive"))
      (node (ref "R56") (pin "1") (pinfunction "1_1") (pintype "passive"))
      (node (ref "R60") (pin "1") (pinfunction "1_1") (pintype "passive"))
      (node (ref "U3") (pin "2") (pinfunction "VSS_2") (pintype "bidirectional"))
      (node (ref "U4") (pin "2") (pinfunction "VSS_2") (pintype "bidirectional"))
      (node (ref "U4") (pin "6") (pinfunction "AO_6") (pintype "bidirectional"))
      (node (ref "USB1") (pin "5") (pinfunction "GND_5") (pintype "bidirectional"))
      (node (ref "USB1") (pin "S1") (pinfunction "GND_S1") (pintype "bidirectional"))
      (node (ref "USB1") (pin "S2") (pinfunction "GND_S2") (pintype "bidirectional"))
      (node (ref "USB1") (pin "S3") (pinfunction "GND_S3") (pintype "bidirectional"))
      (node (ref "USB1") (pin "S4") (pinfunction "GND_S4") (pintype "bidirectional"))
      (node (ref "USB1") (pin "S5") (pinfunction "GND_S5") (pintype "bidirectional"))
      (node (ref "USB1") (pin "S6") (pinfunction "GND_S6") (pintype "bidirectional"))
      (node (ref "X1") (pin "1") (pinfunction "1_1") (pintype "power_in"))
      (node (ref "X1") (pin "3") (pinfunction "3_3") (pintype "power_in"))
      (node (ref "X2") (pin "P$2") (pinfunction "GND1_P$2") (pintype "power_in"))
      (node (ref "X2") (pin "P$4") (pinfunction "GND2_P$4") (pintype "power_in"))
      (node (ref "X4") (pin "3") (pinfunction "B_3") (pintype "passive"))
      (node (ref "X5") (pin "3") (pinfunction "B_3") (pintype "passive"))
    )
    (net (code "22") (name "GPSGND") (class "Default")
      (node (ref "C30") (pin "2") (pinfunction "2_2") (pintype "passive"))
      (node (ref "C31") (pin "2") (pinfunction "2_2") (pintype "passive"))
      (node (ref "C41") (pin "2") (pinfunction "2_2") (pintype "passive"))
      (node (ref "J5") (pin "1") (pinfunction "GND_1") (pintype "passive"))
      (node (ref "L8") (pin "2") (pinfunction "2_2") (pintype "passive"))
      (node (ref "U1") (pin "1") (pinfunction "GND_1") (pintype "power_in"))
      (node (ref "U1") (pin "10") (pinfunction "GND_10") (pintype "power_in"))
      (node (ref "U1") (pin "12") (pinfunction "GND_12") (pintype "power_in"))
    )
    (net (code "23") (name "GPSPPS") (class "Default")
      (node (ref "CPU") (pin "P$14") (pinfunction "PA0_P$14") (pintype "bidirectional"))
      (node (ref "U1") (pin "4") (pinfunction "1PSS_4") (pintype "output"))
    )
    (net (code "24") (name "GPSRX") (class "Default")
      (node (ref "J6") (pin "8") (pinfunction "8_8") (pintype "passive"))
      (node (ref "U1") (pin "3") (pinfunction "RXD1_3") (pintype "bidirectional"))
    )
    (net (code "25") (name "GPSTX") (class "Default")
      (node (ref "J6") (pin "10") (pinfunction "10_10") (pintype "passive"))
      (node (ref "U1") (pin "2") (pinfunction "TXD1_2") (pintype "output"))
    )
    (net (code "26") (name "HV1EN") (class "Default")
      (node (ref "IC17") (pin "1") (pinfunction "ENA_1") (pintype "bidirectional"))
      (node (ref "PSU") (pin "P$9") (pinfunction "PC1_P$9") (pintype "bidirectional"))
    )
    (net (code "27") (name "HV1PWM") (class "Default")
      (node (ref "IC17") (pin "2") (pinfunction "INA_2") (pintype "bidirectional"))
      (node (ref "PSU") (pin "P$14") (pinfunction "PA0_P$14") (pintype "bidirectional"))
    )
    (net (code "28") (name "HV2EN") (class "Default")
      (node (ref "IC17") (pin "8") (pinfunction "ENB_8") (pintype "bidirectional"))
      (node (ref "PSU") (pin "P$10") (pinfunction "PC2_P$10") (pintype "bidirectional"))
    )
    (net (code "29") (name "HV2PWM") (class "Default")
      (node (ref "IC17") (pin "4") (pinfunction "INB_4") (pintype "bidirectional"))
      (node (ref "PSU") (pin "P$17") (pinfunction "PA3_P$17") (pintype "bidirectional"))
    )
    (net (code "30") (name "ID_SC") (class "Default")
      (node (ref "IC11") (pin "1") (pinfunction "SCL_1") (pintype "input"))
      (node (ref "J6") (pin "28") (pinfunction "28_28") (pintype "passive"))
    )
    (net (code "31") (name "ID_SD") (class "Default")
      (node (ref "IC11") (pin "3") (pinfunction "SDA_3") (pintype "bidirectional"))
      (node (ref "J6") (pin "27") (pinfunction "27_27") (pintype "passive"))
    )
    (net (code "32") (name "LED1") (class "Default")
      (node (ref "CPU") (pin "P$9") (pinfunction "PC1_P$9") (pintype "bidirectional"))
      (node (ref "R35") (pin "1") (pinfunction "1_1") (pintype "passive"))
    )
    (net (code "33") (name "LED2") (class "Default")
      (node (ref "CPU") (pin "P$10") (pinfunction "PC2_P$10") (pintype "bidirectional"))
      (node (ref "R34") (pin "1") (pinfunction "1_1") (pintype "passive"))
    )
    (net (code "34") (name "LEDB") (class "Default")
      (node (ref "PSU") (pin "P$41") (pinfunction "PA8_P$41") (pintype "bidirectional"))
      (node (ref "R22") (pin "1") (pinfunction "1_1") (pintype "passive"))
      (node (ref "R3") (pin "1") (pinfunction "1_1") (pintype "passive"))
    )
    (net (code "35") (name "Net-(C2-Pad1)") (class "Default")
      (node (ref "C2") (pin "1") (pinfunction "1_1") (pintype "passive"))
      (node (ref "R1") (pin "2") (pinfunction "2_2") (pintype "passive"))
      (node (ref "R2") (pin "1") (pinfunction "1_1") (pintype "passive"))
    )
    (net (code "36") (name "Net-(C21-Pad1)") (class "Default")
      (node (ref "C21") (pin "1") (pinfunction "1_1") (pintype "passive"))
      (node (ref "R15") (pin "2") (pinfunction "2_2") (pintype "passive"))
      (node (ref "R16") (pin "1") (pinfunction "1_1") (pintype "passive"))
    )
    (net (code "37") (name "Net-(C43-Pad1)") (class "Default")
      (node (ref "C43") (pin "1") (pinfunction "1_1") (pintype "passive"))
      (node (ref "R42") (pin "1") (pinfunction "1_1") (pintype "passive"))
      (node (ref "R43") (pin "2") (pinfunction "2_2") (pintype "passive"))
    )
    (net (code "38") (name "Net-(C49-Pad1)") (class "Default")
      (node (ref "C49") (pin "1") (pinfunction "1_1") (pintype "passive"))
      (node (ref "R52") (pin "1") (pinfunction "1_1") (pintype "passive"))
      (node (ref "R53") (pin "2") (pinfunction "2_2") (pintype "passive"))
    )
    (net (code "39") (name "Net-(CPU-PH0_XI)") (class "Default")
      (node (ref "C77") (pin "2") (pinfunction "2_2") (pintype "passive"))
      (node (ref "CPU") (pin "P$5") (pinfunction "PH0_XI_P$5") (pintype "bidirectional"))
      (node (ref "X2") (pin "P$3") (pinfunction "P$2_P$3") (pintype "passive"))
    )
    (net (code "40") (name "Net-(CPU-PH1_XO)") (class "Default")
      (node (ref "C78") (pin "2") (pinfunction "2_2") (pintype "passive"))
      (node (ref "CPU") (pin "P$6") (pinfunction "PH1_XO_P$6") (pintype "bidirectional"))
      (node (ref "X2") (pin "P$1") (pinfunction "P$1_P$1") (pintype "passive"))
    )
    (net (code "41") (name "Net-(CPU-VCAP)") (class "Default")
      (node (ref "C79") (pin "2") (pinfunction "2_2") (pintype "passive"))
      (node (ref "CPU") (pin "P$30") (pinfunction "VCAP_P$30") (pintype "power_in"))
    )
    (net (code "42") (name "Net-(D1-Pad+)") (class "Default")
      (node (ref "D1") (pin "+") (pinfunction "+_+") (pintype "passive"))
      (node (ref "R35") (pin "2") (pinfunction "2_2") (pintype "passive"))
    )
    (net (code "43") (name "Net-(D8-A)") (class "Default")
      (node (ref "D8") (pin "P$2") (pinfunction "A_P$2") (pintype "bidirectional"))
      (node (ref "L10") (pin "1") (pinfunction "1_1") (pintype "passive"))
    )
    (net (code "44") (name "Net-(D9-Pad+)") (class "Default")
      (node (ref "D9") (pin "+") (pinfunction "+_+") (pintype "passive"))
      (node (ref "R45") (pin "2") (pinfunction "2_2") (pintype "passive"))
    )
    (net (code "45") (name "Net-(D10-Pad+)") (class "Default")
      (node (ref "D10") (pin "+") (pinfunction "+_+") (pintype "passive"))
      (node (ref "R22") (pin "2") (pinfunction "2_2") (pintype "passive"))
    )
    (net (code "46") (name "Net-(D11-Pad+)") (class "Default")
      (node (ref "D11") (pin "+") (pinfunction "+_+") (pintype "passive"))
      (node (ref "R34") (pin "2") (pinfunction "2_2") (pintype "passive"))
    )
    (net (code "47") (name "Net-(D12-Pad+)") (class "Default")
      (node (ref "D12") (pin "+") (pinfunction "+_+") (pintype "passive"))
      (node (ref "R3") (pin "2") (pinfunction "2_2") (pintype "passive"))
    )
    (net (code "48") (name "Net-(D13-A)") (class "Default")
      (node (ref "D13") (pin "2") (pinfunction "A_2") (pintype "passive"))
      (node (ref "L2") (pin "2") (pinfunction "2_2") (pintype "passive"))
      (node (ref "Q1") (pin "3") (pinfunction "D_3") (pintype "passive"))
    )
    (net (code "49") (name "Net-(D13-K)") (class "Default")
      (node (ref "C9") (pin "1") (pinfunction "1_1") (pintype "passive"))
      (node (ref "D13") (pin "1") (pinfunction "K_1") (pintype "passive"))
      (node (ref "R20") (pin "2") (pinfunction "2_2") (pintype "passive"))
    )
    (net (code "50") (name "Net-(D14-A)") (class "Default")
      (node (ref "D14") (pin "2") (pinfunction "A_2") (pintype "passive"))
      (node (ref "L9") (pin "2") (pinfunction "2_2") (pintype "passive"))
      (node (ref "Q2") (pin "3") (pinfunction "D_3") (pintype "passive"))
    )
    (net (code "51") (name "Net-(D14-K)") (class "Default")
      (node (ref "C44") (pin "1") (pinfunction "1_1") (pintype "passive"))
      (node (ref "D14") (pin "1") (pinfunction "K_1") (pintype "passive"))
      (node (ref "R47") (pin "2") (pinfunction "2_2") (pintype "passive"))
    )
    (net (code "52") (name "Net-(D15-A)") (class "Default")
      (node (ref "D15") (pin "P$2") (pinfunction "A_P$2") (pintype "bidirectional"))
      (node (ref "USB1") (pin "1") (pinfunction "VCC_1") (pintype "bidirectional"))
    )
    (net (code "53") (name "Net-(IC$3-OUTA)") (class "Default")
      (node (ref "IC$3") (pin "1") (pinfunction "OUTA_1") (pintype "output"))
      (node (ref "R36") (pin "1") (pinfunction "1_1") (pintype "passive"))
    )
    (net (code "54") (name "Net-(IC$3-OUTB)") (class "Default")
      (node (ref "IC$3") (pin "7") (pinfunction "OUTB_7") (pintype "output"))
      (node (ref "R37") (pin "1") (pinfunction "1_1") (pintype "passive"))
    )
    (net (code "55") (name "Net-(IC1A-OUT)") (class "Default")
      (node (ref "C16") (pin "1") (pinfunction "1_1") (pintype "passive"))
      (node (ref "C17") (pin "2") (pinfunction "2_2") (pintype "passive"))
      (node (ref "IC1") (pin "1") (pinfunction "OUT_1") (pintype "output"))
      (node (ref "R28") (pin "2") (pinfunction "2_2") (pintype "passive"))
    )
    (net (code "56") (name "Net-(IC1B-IN+)") (class "Default")
      (node (ref "C20") (pin "1") (pinfunction "1_1") (pintype "passive"))
      (node (ref "IC1") (pin "5") (pinfunction "IN+_5") (pintype "input"))
      (node (ref "R9") (pin "2") (pinfunction "2_2") (pintype "passive"))
    )
    (net (code "57") (name "Net-(IC1B-IN-)") (class "Default")
      (node (ref "C18") (pin "1") (pinfunction "1_1") (pintype "passive"))
      (node (ref "IC1") (pin "6") (pinfunction "IN-_6") (pintype "input"))
      (node (ref "R26") (pin "2") (pinfunction "2_2") (pintype "passive"))
      (node (ref "R27") (pin "1") (pinfunction "1_1") (pintype "passive"))
    )
    (net (code "58") (name "Net-(IC1B-OUT)") (class "Default")
      (node (ref "C18") (pin "2") (pinfunction "2_2") (pintype "passive"))
      (node (ref "IC1") (pin "7") (pinfunction "OUT_7") (pintype "output"))
      (node (ref "R27") (pin "2") (pinfunction "2_2") (pintype "passive"))
      (node (ref "R7") (pin "1") (pinfunction "1_1") (pintype "passive"))
    )
    (net (code "59") (name "Net-(IC2A-OUT)") (class "Default")
      (node (ref "C1") (pin "1") (pinfunction "1_1") (pintype "passive"))
      (node (ref "C4") (pin "2") (pinfunction "2_2") (pintype "passive"))
      (node (ref "IC2") (pin "1") (pinfunction "OUT_1") (pintype "output"))
      (node (ref "R24") (pin "2") (pinfunction "2_2") (pintype "passive"))
    )
    (net (code "60") (name "Net-(IC2B-IN-)") (class "Default")
      (node (ref "C23") (pin "1") (pinfunction "1_1") (pintype "passive"))
      (node (ref "IC2") (pin "6") (pinfunction "IN-_6") (pintype "input"))
      (node (ref "R17") (pin "2") (pinfunction "2_2") (pintype "passive"))
      (node (ref "R18") (pin "1") (pinfunction "1_1") (pintype "passive"))
    )
    (net (code "61") (name "Net-(IC2B-OUT)") (class "Default")
      (node (ref "C23") (pin "2") (pinfunction "2_2") (pintype "passive"))
      (node (ref "IC2") (pin "7") (pinfunction "OUT_7") (pintype "output"))
      (node (ref "R18") (pin "2") (pinfunction "2_2") (pintype "passive"))
      (node (ref "R8") (pin "1") (pinfunction "1_1") (pintype "passive"))
    )
    (net (code "62") (name "Net-(IC3-BP)") (class "Default")
      (node (ref "C8") (pin "1") (pinfunction "1_1") (pintype "passive"))
      (node (ref "IC3") (pin "4") (pinfunction "BP_4") (pintype "input"))
    )
    (net (code "63") (name "Net-(IC4-CV)") (class "Default")
      (node (ref "C39") (pin "2") (pinfunction "2_2") (pintype "passive"))
      (node (ref "IC4") (pin "5") (pinfunction "CV_5") (pintype "input"))
    )
    (net (code "64") (name "Net-(IC4-DIS)") (class "Default")
      (node (ref "C40") (pin "2") (pinfunction "2_2") (pintype "passive"))
      (node (ref "IC4") (pin "6") (pinfunction "THR_6") (pintype "input"))
      (node (ref "IC4") (pin "7") (pinfunction "DIS_7") (pintype "input"))
      (node (ref "R39") (pin "1") (pinfunction "1_1") (pintype "passive"))
    )
    (net (code "65") (name "Net-(IC4-TR)") (class "Default")
      (node (ref "IC4") (pin "2") (pinfunction "TR_2") (pintype "input"))
      (node (ref "IC7") (pin "4") (pinfunction "O_4") (pintype "output"))
      (node (ref "R38") (pin "1") (pinfunction "1_1") (pintype "passive"))
    )
    (net (code "66") (name "Net-(IC5-CV)") (class "Default")
      (node (ref "C51") (pin "2") (pinfunction "2_2") (pintype "passive"))
      (node (ref "IC5") (pin "5") (pinfunction "CV_5") (pintype "input"))
    )
    (net (code "67") (name "Net-(IC5-DIS)") (class "Default")
      (node (ref "C52") (pin "2") (pinfunction "2_2") (pintype "passive"))
      (node (ref "IC5") (pin "6") (pinfunction "THR_6") (pintype "input"))
      (node (ref "IC5") (pin "7") (pinfunction "DIS_7") (pintype "input"))
      (node (ref "R55") (pin "1") (pinfunction "1_1") (pintype "passive"))
    )
    (net (code "68") (name "Net-(IC5-TR)") (class "Default")
      (node (ref "IC5") (pin "2") (pinfunction "TR_2") (pintype "input"))
      (node (ref "IC8") (pin "4") (pinfunction "O_4") (pintype "output"))
      (node (ref "R54") (pin "1") (pinfunction "1_1") (pintype "passive"))
    )
    (net (code "69") (name "Net-(IC6-CV)") (class "Default")
      (node (ref "C54") (pin "2") (pinfunction "2_2") (pintype "passive"))
      (node (ref "IC6") (pin "5") (pinfunction "CV_5") (pintype "input"))
    )
    (net (code "70") (name "Net-(IC6-DIS)") (class "Default")
      (node (ref "C55") (pin "2") (pinfunction "2_2") (pintype "passive"))
      (node (ref "IC6") (pin "6") (pinfunction "THR_6") (pintype "input"))
      (node (ref "IC6") (pin "7") (pinfunction "DIS_7") (pintype "input"))
      (node (ref "R59") (pin "1") (pinfunction "1_1") (pintype "passive"))
    )
    (net (code "71") (name "Net-(IC6-TR)") (class "Default")
      (node (ref "IC6") (pin "2") (pinfunction "TR_2") (pintype "input"))
      (node (ref "IC9") (pin "4") (pinfunction "O_4") (pintype "output"))
      (node (ref "R58") (pin "1") (pinfunction "1_1") (pintype "passive"))
    )
    (net (code "72") (name "Net-(IC10A-IN-)") (class "Default")
      (node (ref "C72") (pin "1") (pinfunction "1_1") (pintype "passive"))
      (node (ref "IC10") (pin "2") (pinfunction "IN-_2") (pintype "input"))
      (node (ref "R64") (pin "2") (pinfunction "2_2") (pintype "passive"))
      (node (ref "R65") (pin "1") (pinfunction "1_1") (pintype "passive"))
    )
    (net (code "73") (name "Net-(IC10A-OUT)") (class "Default")
      (node (ref "C72") (pin "2") (pinfunction "2_2") (pintype "passive"))
      (node (ref "IC10") (pin "1") (pinfunction "OUT_1") (pintype "output"))
      (node (ref "R65") (pin "2") (pinfunction "2_2") (pintype "passive"))
      (node (ref "R66") (pin "1") (pinfunction "1_1") (pintype "passive"))
    )
    (net (code "74") (name "Net-(IC10B-IN-)") (class "Default")
      (node (ref "C75") (pin "1") (pinfunction "1_1") (pintype "passive"))
      (node (ref "IC10") (pin "6") (pinfunction "IN-_6") (pintype "input"))
      (node (ref "R73") (pin "2") (pinfunction "2_2") (pintype "passive"))
      (node (ref "R74") (pin "1") (pinfunction "1_1") (pintype "passive"))
    )
    (net (code "75") (name "Net-(IC10B-OUT)") (class "Default")
      (node (ref "C75") (pin "2") (pinfunction "2_2") (pintype "passive"))
      (node (ref "IC10") (pin "7") (pinfunction "OUT_7") (pintype "output"))
      (node (ref "R74") (pin "2") (pinfunction "2_2") (pintype "passive"))
      (node (ref "R75") (pin "1") (pinfunction "1_1") (pintype "passive"))
    )
    (net (code "76") (name "Net-(IC16-C1)") (class "Default")
      (node (ref "C27") (pin "1") (pinfunction "1_1") (pintype "passive"))
      (node (ref "IC16") (pin "P$15") (pinfunction "C1_P$15") (pintype "bidirectional"))
    )
    (net (code "77") (name "Net-(IC16-SETC)") (class "Default")
      (node (ref "C26") (pin "2") (pinfunction "2_2") (pintype "passive"))
      (node (ref "IC16") (pin "P$2") (pinfunction "SETC_P$2") (pintype "bidirectional"))
    )
    (net (code "78") (name "Net-(IC16-SETP)") (class "Default")
      (node (ref "C26") (pin "1") (pinfunction "1_1") (pintype "passive"))
      (node (ref "IC16") (pin "P$3") (pinfunction "SETP_P$3") (pintype "bidirectional"))
    )
    (net (code "79") (name "Net-(IC17-OUTA)") (class "Default")
      (node (ref "IC17") (pin "7") (pinfunction "OUTA_7") (pintype "bidirectional"))
      (node (ref "R10") (pin "2") (pinfunction "2_2") (pintype "passive"))
    )
    (net (code "80") (name "Net-(IC17-OUTB)") (class "Default")
      (node (ref "IC17") (pin "5") (pinfunction "OUTB_5") (pintype "bidirectional"))
      (node (ref "R12") (pin "2") (pinfunction "2_2") (pintype "passive"))
    )
    (net (code "81") (name "Net-(J3-GND-Pad1)") (class "Default")
      (node (ref "J3") (pin "1") (pinfunction "GND_1") (pintype "passive"))
      (node (ref "R71") (pin "1") (pinfunction "1_1") (pintype "passive"))
    )
    (net (code "82") (name "Net-(J3-SIG)") (class "Default")
      (node (ref "J3") (pin "5") (pinfunction "SIG_5") (pintype "passive"))
      (node (ref "R5") (pin "2") (pinfunction "2_2") (pintype "passive"))
    )
    (net (code "83") (name "Net-(J4-GND-Pad1)") (class "Default")
      (node (ref "J4") (pin "1") (pinfunction "GND_1") (pintype "passive"))
      (node (ref "R77") (pin "1") (pinfunction "1_1") (pintype "passive"))
    )
    (net (code "84") (name "Net-(J4-SIG)") (class "Default")
      (node (ref "J4") (pin "5") (pinfunction "SIG_5") (pintype "passive"))
      (node (ref "R25") (pin "2") (pinfunction "2_2") (pintype "passive"))
    )
    (net (code "85") (name "Net-(J5-SIG)") (class "Default")
      (node (ref "C30") (pin "1") (pinfunction "1_1") (pintype "passive"))
      (node (ref "J5") (pin "5") (pinfunction "SIG_5") (pintype "passive"))
      (node (ref "L3") (pin "1") (pinfunction "1_1") (pintype "passive"))
      (node (ref "R31") (pin "1") (pinfunction "1_1") (pintype "passive"))
    )
    (net (code "86") (name "Net-(L3-Pad2)") (class "Default")
      (node (ref "L3") (pin "2") (pinfunction "2_2") (pintype "passive"))
      (node (ref "R30") (pin "2") (pinfunction "2_2") (pintype "passive"))
    )
    (net (code "87") (name "Net-(PSU-PC0)") (class "Default")
      (node (ref "PSU") (pin "P$8") (pinfunction "PC0_P$8") (pintype "bidirectional"))
      (node (ref "R45") (pin "1") (pinfunction "1_1") (pintype "passive"))
    )
    (net (code "88") (name "Net-(PSU-VCAP)") (class "Default")
      (node (ref "C71") (pin "2") (pinfunction "2_2") (pintype "passive"))
      (node (ref "PSU") (pin "P$30") (pinfunction "VCAP_P$30") (pintype "power_in"))
    )
    (net (code "89") (name "Net-(Q1-G)") (class "Default")
      (node (ref "Q1") (pin "1") (pinfunction "G_1") (pintype "passive"))
      (node (ref "R10") (pin "1") (pinfunction "1_1") (pintype "passive"))
    )
    (net (code "90") (name "Net-(Q2-G)") (class "Default")
      (node (ref "Q2") (pin "1") (pinfunction "G_1") (pintype "passive"))
      (node (ref "R12") (pin "1") (pinfunction "1_1") (pintype "passive"))
    )
    (net (code "91") (name "Net-(R4-Pad2)") (class "Default")
      (node (ref "R4") (pin "2") (pinfunction "2_2") (pintype "passive"))
      (node (ref "R67") (pin "1") (pinfunction "1_1") (pintype "passive"))
    )
    (net (code "92") (name "Net-(R32-Pad1)") (class "Default")
      (node (ref "R32") (pin "1") (pinfunction "1_1") (pintype "passive"))
      (node (ref "R67") (pin "2") (pinfunction "2_2") (pintype "passive"))
    )
    (net (code "93") (name "Net-(SIPM1X1_BOT-C)") (class "Default")
      (node (ref "C22") (pin "1") (pinfunction "1_1") (pintype "passive"))
      (node (ref "J2") (pin "1") (pinfunction "GND_1") (pintype "passive"))
      (node (ref "J2") (pin "3") (pinfunction "GND_3") (pintype "passive"))
      (node (ref "R16") (pin "2") (pinfunction "2_2") (pintype "passive"))
      (node (ref "SIPM1X1_BOT") (pin "P$1") (pinfunction "C_P$1") (pintype "passive"))
      (node (ref "SIPM3X3_BOT") (pin "P$1") (pinfunction "C_P$1") (pintype "passive"))
    )
    (net (code "94") (name "Net-(SIPM1X1_TOP-C)") (class "Default")
      (node (ref "C3") (pin "1") (pinfunction "1_1") (pintype "passive"))
      (node (ref "J1") (pin "1") (pinfunction "GND_1") (pintype "passive"))
      (node (ref "J1") (pin "3") (pinfunction "GND_3") (pintype "passive"))
      (node (ref "R2") (pin "2") (pinfunction "2_2") (pintype "passive"))
      (node (ref "SIPM1X1_TOP") (pin "P$1") (pinfunction "C_P$1") (pintype "passive"))
      (node (ref "SIPM3X3_TOP") (pin "P$1") (pinfunction "C_P$1") (pintype "passive"))
    )
    (net (code "95") (name "Net-(U1-RF_IN)") (class "Default")
      (node (ref "C31") (pin "1") (pinfunction "1_1") (pintype "passive"))
      (node (ref "R31") (pin "2") (pinfunction "2_2") (pintype "passive"))
      (node (ref "U1") (pin "11") (pinfunction "RF_IN_11") (pintype "bidirectional"))
    )
    (net (code "96") (name "Net-(U1-VCC_RF)") (class "Default")
      (node (ref "R30") (pin "1") (pinfunction "1_1") (pintype "passive"))
      (node (ref "U1") (pin "14") (pinfunction "VCC_RF_14") (pintype "output"))
    )
    (net (code "97") (name "PI_FLAG0") (class "Default")
      (node (ref "CPU") (pin "P$39") (pinfunction "PC8_P$39") (pintype "bidirectional"))
      (node (ref "J6") (pin "7") (pinfunction "7_7") (pintype "passive"))
    )
    (net (code "98") (name "PI_FLAG1") (class "Default")
      (node (ref "CPU") (pin "P$40") (pinfunction "PC9_P$40") (pintype "bidirectional"))
      (node (ref "J6") (pin "12") (pinfunction "12_12") (pintype "passive"))
    )
    (net (code "99") (name "PI_FLAG2") (class "Default")
      (node (ref "CPU") (pin "P$51") (pinfunction "PC10_P$51") (pintype "bidirectional"))
      (node (ref "J6") (pin "15") (pinfunction "15_15") (pintype "passive"))
    )
    (net (code "100") (name "PSUF1") (class "Default")
      (node (ref "C33") (pin "1") (pinfunction "1_1") (pintype "passive"))
      (node (ref "C36") (pin "2") (pinfunction "2_2") (pintype "passive"))
      (node (ref "C5") (pin "1") (pinfunction "1_1") (pintype "passive"))
      (node (ref "C65") (pin "2") (pinfunction "2_2") (pintype "passive"))
      (node (ref "C66") (pin "2") (pinfunction "2_2") (pintype "passive"))
      (node (ref "C67") (pin "2") (pinfunction "2_2") (pintype "passive"))
      (node (ref "C68") (pin "2") (pinfunction "2_2") (pintype "passive"))
      (node (ref "IC$3") (pin "8") (pinfunction "VDD_8") (pintype "power_in"))
      (node (ref "L4") (pin "1") (pinfunction "1_1") (pintype "passive"))
      (node (ref "U3") (pin "3") (pinfunction "VDD_3") (pintype "bidirectional"))
      (node (ref "U3") (pin "6") (pinfunction "AO_6") (pintype "bidirectional"))
      (node (ref "U4") (pin "3") (pinfunction "VDD_3") (pintype "bidirectional"))
    )
    (net (code "101") (name "PSUF2") (class "Default")
      (node (ref "C37") (pin "1") (pinfunction "1_1") (pintype "passive"))
      (node (ref "C56") (pin "2") (pinfunction "2_2") (pintype "passive"))
      (node (ref "C57") (pin "2") (pinfunction "2_2") (pintype "passive"))
      (node (ref "C58") (pin "2") (pinfunction "2_2") (pintype "passive"))
      (node (ref "IC7") (pin "5") (pinfunction "VCC_5") (pintype "power_in"))
      (node (ref "IC8") (pin "5") (pinfunction "VCC_5") (pintype "power_in"))
      (node (ref "IC9") (pin "5") (pinfunction "VCC_5") (pintype "power_in"))
      (node (ref "L5") (pin "1") (pinfunction "1_1") (pintype "passive"))
    )
    (net (code "102") (name "PSUF3") (class "Default")
      (node (ref "C41") (pin "1") (pinfunction "1_1") (pintype "passive"))
      (node (ref "C42") (pin "1") (pinfunction "1_1") (pintype "passive"))
      (node (ref "L6") (pin "1") (pinfunction "1_1") (pintype "passive"))
      (node (ref "U1") (pin "6") (pinfunction "V_BCKP_6") (pintype "power_in"))
      (node (ref "U1") (pin "8") (pinfunction "VCC_8") (pintype "power_in"))
      (node (ref "U1") (pin "9") (pinfunction "RESET_9") (pintype "bidirectional"))
    )
    (net (code "103") (name "PSUFB1") (class "Default")
      (node (ref "PSU") (pin "P$15") (pinfunction "PA1_P$15") (pintype "bidirectional"))
      (node (ref "R11") (pin "2") (pinfunction "2_2") (pintype "passive"))
      (node (ref "R21") (pin "1") (pinfunction "1_1") (pintype "passive"))
    )
    (net (code "104") (name "PSUFB2") (class "Default")
      (node (ref "PSU") (pin "P$16") (pinfunction "PA2_P$16") (pintype "bidirectional"))
      (node (ref "R49") (pin "1") (pinfunction "1_1") (pintype "passive"))
      (node (ref "R50") (pin "2") (pinfunction "2_2") (pintype "passive"))
    )
    (net (code "105") (name "PSU_BOOT0") (class "Default")
      (node (ref "J6") (pin "13") (pinfunction "13_13") (pintype "passive"))
      (node (ref "PSU") (pin "P$60") (pinfunction "BOOT0_P$60") (pintype "bidirectional"))
    )
    (net (code "106") (name "PSU_JTCK-SWCLK") (class "Default")
      (node (ref "PSU") (pin "P$49") (pinfunction "PA14_P$49") (pintype "bidirectional"))
      (node (ref "X5") (pin "7") (pinfunction "B_7") (pintype "passive"))
    )
    (net (code "107") (name "PSU_JTDO-SWO") (class "Default")
      (node (ref "PSU") (pin "P$55") (pinfunction "PB3_P$55") (pintype "bidirectional"))
      (node (ref "X5") (pin "2") (pinfunction "B_2") (pintype "passive"))
    )
    (net (code "108") (name "PSU_JTMS-SWDIO") (class "Default")
      (node (ref "PSU") (pin "P$46") (pinfunction "PA13_P$46") (pintype "bidirectional"))
      (node (ref "X5") (pin "5") (pinfunction "B_5") (pintype "passive"))
    )
    (net (code "109") (name "PSU_NRST") (class "Default")
      (node (ref "C80") (pin "1") (pinfunction "1_1") (pintype "passive"))
      (node (ref "J6") (pin "11") (pinfunction "11_11") (pintype "passive"))
      (node (ref "PSU") (pin "P$7") (pinfunction "NRST_P$7") (pintype "bidirectional"))
      (node (ref "X5") (pin "8") (pinfunction "B_8") (pintype "passive"))
    )
    (net (code "110") (name "PSU_SYS_JTDI") (class "Default")
      (node (ref "PSU") (pin "P$50") (pinfunction "PA15_P$50") (pintype "bidirectional"))
      (node (ref "X5") (pin "6") (pinfunction "B_6") (pintype "passive"))
    )
    (net (code "111") (name "PSU_SYS_JTRST") (class "Default")
      (node (ref "PSU") (pin "P$56") (pinfunction "PB4_P$56") (pintype "bidirectional"))
      (node (ref "X5") (pin "4") (pinfunction "B_4") (pintype "passive"))
    )
    (net (code "112") (name "SCL0") (class "Default")
      (node (ref "IC14") (pin "2") (pinfunction "SCL_2") (pintype "bidirectional"))
      (node (ref "IC15") (pin "P$6") (pinfunction "SCL_P$6") (pintype "bidirectional"))
      (node (ref "IC16") (pin "P$4") (pinfunction "SCL/SPC_P$4") (pintype "bidirectional"))
      (node (ref "J6") (pin "5") (pinfunction "5_5") (pintype "passive"))
      (node (ref "R23") (pin "2") (pinfunction "2_2") (pintype "passive"))
      (node (ref "U3") (pin "5") (pinfunction "SCL_5") (pintype "bidirectional"))
      (node (ref "U4") (pin "5") (pinfunction "SCL_5") (pintype "bidirectional"))
    )
    (net (code "113") (name "SDA0") (class "Default")
      (node (ref "IC14") (pin "4") (pinfunction "SDA_4") (pintype "bidirectional"))
      (node (ref "IC15") (pin "P$1") (pinfunction "SDA_P$1") (pintype "bidirectional"))
      (node (ref "IC16") (pin "P$6") (pinfunction "SDA/SDI_P$6") (pintype "bidirectional"))
      (node (ref "J6") (pin "3") (pinfunction "3_3") (pintype "passive"))
      (node (ref "R29") (pin "1") (pinfunction "1_1") (pintype "passive"))
      (node (ref "U3") (pin "4") (pinfunction "SDA_4") (pintype "bidirectional"))
      (node (ref "U4") (pin "4") (pinfunction "SDA_4") (pintype "bidirectional"))
    )
    (net (code "114") (name "SIG1A") (class "Default")
      (node (ref "C17") (pin "1") (pinfunction "1_1") (pintype "passive"))
      (node (ref "D4") (pin "3") (pinfunction "C1A2_3") (pintype "passive"))
      (node (ref "IC1") (pin "2") (pinfunction "IN-_2") (pintype "input"))
      (node (ref "J1") (pin "2") (pinfunction "SIG_2") (pintype "passive"))
      (node (ref "R28") (pin "1") (pinfunction "1_1") (pintype "passive"))
      (node (ref "SIPM1X1_TOP") (pin "P$2") (pinfunction "A_P$2") (pintype "passive"))
      (node (ref "SIPM3X3_TOP") (pin "P$2") (pinfunction "A_P$2") (pintype "passive"))
    )
    (net (code "115") (name "SIG1B") (class "Default")
      (node (ref "C4") (pin "1") (pinfunction "1_1") (pintype "passive"))
      (node (ref "D3") (pin "3") (pinfunction "C1A2_3") (pintype "passive"))
      (node (ref "IC2") (pin "2") (pinfunction "IN-_2") (pintype "input"))
      (node (ref "J2") (pin "2") (pinfunction "SIG_2") (pintype "passive"))
      (node (ref "R24") (pin "1") (pinfunction "1_1") (pintype "passive"))
      (node (ref "SIPM1X1_BOT") (pin "P$2") (pinfunction "A_P$2") (pintype "passive"))
      (node (ref "SIPM3X3_BOT") (pin "P$2") (pinfunction "A_P$2") (pintype "passive"))
    )
    (net (code "116") (name "SIG2A") (class "Default")
      (node (ref "IC$3") (pin "3") (pinfunction "INA+_3") (pintype "input"))
      (node (ref "R7") (pin "2") (pinfunction "2_2") (pintype "passive"))
    )
    (net (code "117") (name "SIG2B") (class "Default")
      (node (ref "IC$3") (pin "5") (pinfunction "INB+_5") (pintype "input"))
      (node (ref "R8") (pin "2") (pinfunction "2_2") (pintype "passive"))
    )
    (net (code "118") (name "SLOWAOUT") (class "Default")
      (node (ref "CPU") (pin "P$23") (pinfunction "PA7_P$23") (pintype "bidirectional"))
      (node (ref "R5") (pin "1") (pinfunction "1_1") (pintype "passive"))
      (node (ref "R66") (pin "2") (pinfunction "2_2") (pintype "passive"))
    )
    (net (code "119") (name "SLOWBOUT") (class "Default")
      (node (ref "CPU") (pin "P$26") (pinfunction "PB0_P$26") (pintype "bidirectional"))
      (node (ref "R25") (pin "1") (pinfunction "1_1") (pintype "passive"))
      (node (ref "R75") (pin "2") (pinfunction "2_2") (pintype "passive"))
    )
    (net (code "120") (name "SLOWCHA") (class "Default")
      (node (ref "C16") (pin "2") (pinfunction "2_2") (pintype "passive"))
      (node (ref "R26") (pin "1") (pinfunction "1_1") (pintype "passive"))
      (node (ref "R64") (pin "1") (pinfunction "1_1") (pintype "passive"))
    )
    (net (code "121") (name "SLOWCHB") (class "Default")
      (node (ref "C1") (pin "2") (pinfunction "2_2") (pintype "passive"))
      (node (ref "R17") (pin "1") (pinfunction "1_1") (pintype "passive"))
      (node (ref "R73") (pin "1") (pinfunction "1_1") (pintype "passive"))
    )
    (net (code "122") (name "SPI_CE0") (class "Default")
      (node (ref "CPU") (pin "P$20") (pinfunction "PA4_P$20") (pintype "bidirectional"))
      (node (ref "J6") (pin "24") (pinfunction "24_24") (pintype "passive"))
    )
    (net (code "123") (name "SPI_CE1") (class "Default")
      (node (ref "J6") (pin "26") (pinfunction "26_26") (pintype "passive"))
      (node (ref "PSU") (pin "P$20") (pinfunction "PA4_P$20") (pintype "bidirectional"))
    )
    (net (code "124") (name "SPI_CLK") (class "Default")
      (node (ref "CPU") (pin "P$21") (pinfunction "PA5_P$21") (pintype "bidirectional"))
      (node (ref "J6") (pin "23") (pinfunction "23_23") (pintype "passive"))
      (node (ref "PSU") (pin "P$21") (pinfunction "PA5_P$21") (pintype "bidirectional"))
    )
    (net (code "125") (name "SPI_MISO") (class "Default")
      (node (ref "CPU") (pin "P$22") (pinfunction "PA6_P$22") (pintype "bidirectional"))
      (node (ref "J6") (pin "21") (pinfunction "21_21") (pintype "passive"))
      (node (ref "PSU") (pin "P$22") (pinfunction "PA6_P$22") (pintype "bidirectional"))
    )
    (net (code "126") (name "SPI_MOSI") (class "Default")
      (node (ref "CPU") (pin "P$57") (pinfunction "PB5_P$57") (pintype "bidirectional"))
      (node (ref "J6") (pin "19") (pinfunction "19_19") (pintype "passive"))
      (node (ref "PSU") (pin "P$23") (pinfunction "PA7_P$23") (pintype "bidirectional"))
    )
    (net (code "127") (name "STRIGA") (class "Default")
      (node (ref "IC7") (pin "1") (pinfunction "I0_1") (pintype "input"))
      (node (ref "IC8") (pin "1") (pinfunction "I0_1") (pintype "input"))
      (node (ref "IC8") (pin "2") (pinfunction "I1_2") (pintype "input"))
      (node (ref "R36") (pin "2") (pinfunction "2_2") (pintype "passive"))
    )
    (net (code "128") (name "STRIGAOUT") (class "Default")
      (node (ref "CPU") (pin "P$29") (pinfunction "PB10_P$29") (pintype "bidirectional"))
      (node (ref "IC5") (pin "3") (pinfunction "Q_3") (pintype "output"))
      (node (ref "R56") (pin "2") (pinfunction "2_2") (pintype "passive"))
      (node (ref "R57") (pin "1") (pinfunction "1_1") (pintype "passive"))
    )
    (net (code "129") (name "STRIGB") (class "Default")
      (node (ref "IC7") (pin "2") (pinfunction "I1_2") (pintype "input"))
      (node (ref "IC9") (pin "1") (pinfunction "I0_1") (pintype "input"))
      (node (ref "IC9") (pin "2") (pinfunction "I1_2") (pintype "input"))
      (node (ref "R37") (pin "2") (pinfunction "2_2") (pintype "passive"))
    )
    (net (code "130") (name "STRIGBOUT") (class "Default")
      (node (ref "CPU") (pin "P$17") (pinfunction "PA3_P$17") (pintype "bidirectional"))
      (node (ref "IC6") (pin "3") (pinfunction "Q_3") (pintype "output"))
      (node (ref "R60") (pin "2") (pinfunction "2_2") (pintype "passive"))
      (node (ref "R61") (pin "1") (pinfunction "1_1") (pintype "passive"))
    )
    (net (code "131") (name "SW") (class "Default")
      (node (ref "C48") (pin "1") (pinfunction "1_1") (pintype "passive"))
      (node (ref "D7") (pin "P$1") (pinfunction "K_P$1") (pintype "bidirectional"))
      (node (ref "IC13") (pin "6") (pinfunction "SW_6") (pintype "output"))
      (node (ref "L11") (pin "P$1") (pinfunction "1_P$1") (pintype "passive"))
    )
    (net (code "132") (name "TRIGOUT") (class "Default")
      (node (ref "CPU") (pin "P$15") (pinfunction "PA1_P$15") (pintype "bidirectional"))
      (node (ref "IC4") (pin "3") (pinfunction "Q_3") (pintype "output"))
      (node (ref "R40") (pin "2") (pinfunction "2_2") (pintype "passive"))
      (node (ref "R41") (pin "1") (pinfunction "1_1") (pintype "passive"))
    )
    (net (code "133") (name "UCDAC0") (class "Default")
      (node (ref "R62") (pin "1") (pinfunction "1_1") (pintype "passive"))
      (node (ref "U3") (pin "1") (pinfunction "VOUT_1") (pintype "bidirectional"))
    )
    (net (code "134") (name "UCDAC0F") (class "Default")
      (node (ref "C59") (pin "2") (pinfunction "2_2") (pintype "passive"))
      (node (ref "C60") (pin "2") (pinfunction "2_2") (pintype "passive"))
      (node (ref "C63") (pin "1") (pinfunction "1_1") (pintype "passive"))
      (node (ref "IC$3") (pin "2") (pinfunction "INA-_2") (pintype "input"))
      (node (ref "R62") (pin "2") (pinfunction "2_2") (pintype "passive"))
    )
    (net (code "135") (name "UCDAC1") (class "Default")
      (node (ref "R63") (pin "1") (pinfunction "1_1") (pintype "passive"))
      (node (ref "U4") (pin "1") (pinfunction "VOUT_1") (pintype "bidirectional"))
    )
    (net (code "136") (name "UCDAC1F") (class "Default")
      (node (ref "C61") (pin "2") (pinfunction "2_2") (pintype "passive"))
      (node (ref "C62") (pin "2") (pinfunction "2_2") (pintype "passive"))
      (node (ref "C64") (pin "1") (pinfunction "1_1") (pintype "passive"))
      (node (ref "IC$3") (pin "6") (pinfunction "INB-_6") (pintype "input"))
      (node (ref "R63") (pin "2") (pinfunction "2_2") (pintype "passive"))
    )
    (net (code "137") (name "VBIAS1") (class "Default")
      (node (ref "C12") (pin "1") (pinfunction "1_1") (pintype "passive"))
      (node (ref "D2") (pin "3") (pinfunction "C_3") (pintype "passive"))
      (node (ref "R1") (pin "1") (pinfunction "1_1") (pintype "passive"))
      (node (ref "R20") (pin "1") (pinfunction "1_1") (pintype "passive"))
      (node (ref "R21") (pin "2") (pinfunction "2_2") (pintype "passive"))
      (node (ref "R42") (pin "2") (pinfunction "2_2") (pintype "passive"))
    )
    (net (code "138") (name "VBIAS2") (class "Default")
      (node (ref "C46") (pin "1") (pinfunction "1_1") (pintype "passive"))
      (node (ref "D5") (pin "3") (pinfunction "C_3") (pintype "passive"))
      (node (ref "R15") (pin "1") (pinfunction "1_1") (pintype "passive"))
      (node (ref "R47") (pin "1") (pinfunction "1_1") (pintype "passive"))
      (node (ref "R49") (pin "2") (pinfunction "2_2") (pintype "passive"))
      (node (ref "R52") (pin "2") (pinfunction "2_2") (pintype "passive"))
    )
    (net (code "139") (name "VIN") (class "Default")
      (node (ref "C47") (pin "+") (pinfunction "+_+") (pintype "passive"))
      (node (ref "D8") (pin "P$1") (pinfunction "K_P$1") (pintype "bidirectional"))
      (node (ref "IC13") (pin "5") (pinfunction "VIN_5") (pintype "input"))
      (node (ref "PC1") (pin "+") (pinfunction "+_+") (pintype "passive"))
      (node (ref "R13") (pin "1") (pinfunction "1_1") (pintype "passive"))
    )
    (net (code "140") (name "VIN+") (class "Default")
      (node (ref "L10") (pin "2") (pinfunction "2_2") (pintype "passive"))
      (node (ref "X1") (pin "2") (pinfunction "2_2") (pintype "power_in"))
    )
    (net (code "141") (name "unconnected-(CPU-PA2-PadP$16)") (class "Default")
      (node (ref "CPU") (pin "P$16") (pinfunction "PA2_P$16") (pintype "bidirectional"))
    )
    (net (code "142") (name "unconnected-(CPU-PA8-PadP$41)") (class "Default")
      (node (ref "CPU") (pin "P$41") (pinfunction "PA8_P$41") (pintype "bidirectional"))
    )
    (net (code "143") (name "unconnected-(CPU-PA9-PadP$42)") (class "Default")
      (node (ref "CPU") (pin "P$42") (pinfunction "PA9_P$42") (pintype "bidirectional"))
    )
    (net (code "144") (name "unconnected-(CPU-PA10-PadP$43)") (class "Default")
      (node (ref "CPU") (pin "P$43") (pinfunction "PA10_P$43") (pintype "bidirectional"))
    )
    (net (code "145") (name "unconnected-(CPU-PA11-PadP$44)") (class "Default")
      (node (ref "CPU") (pin "P$44") (pinfunction "PA11_P$44") (pintype "bidirectional"))
    )
    (net (code "146") (name "unconnected-(CPU-PA12-PadP$45)") (class "Default")
      (node (ref "CPU") (pin "P$45") (pinfunction "PA12_P$45") (pintype "bidirectional"))
    )
    (net (code "147") (name "unconnected-(CPU-PB1-PadP$27)") (class "Default")
      (node (ref "CPU") (pin "P$27") (pinfunction "PB1_P$27") (pintype "bidirectional"))
    )
    (net (code "148") (name "unconnected-(CPU-PB2-PadP$28)") (class "Default")
      (node (ref "CPU") (pin "P$28") (pinfunction "PB2_P$28") (pintype "bidirectional"))
    )
    (net (code "149") (name "unconnected-(CPU-PB6-PadP$58)") (class "Default")
      (node (ref "CPU") (pin "P$58") (pinfunction "PB6_P$58") (pintype "bidirectional"))
    )
    (net (code "150") (name "unconnected-(CPU-PB7-PadP$59)") (class "Default")
      (node (ref "CPU") (pin "P$59") (pinfunction "PB7_P$59") (pintype "bidirectional"))
    )
    (net (code "151") (name "unconnected-(CPU-PB8-PadP$61)") (class "Default")
      (node (ref "CPU") (pin "P$61") (pinfunction "PB8_P$61") (pintype "bidirectional"))
    )
    (net (code "152") (name "unconnected-(CPU-PB9-PadP$62)") (class "Default")
      (node (ref "CPU") (pin "P$62") (pinfunction "PB9_P$62") (pintype "bidirectional"))
    )
    (net (code "153") (name "unconnected-(CPU-PB12-PadP$33)") (class "Default")
      (node (ref "CPU") (pin "P$33") (pinfunction "PB12_P$33") (pintype "bidirectional"))
    )
    (net (code "154") (name "unconnected-(CPU-PB13-PadP$34)") (class "Default")
      (node (ref "CPU") (pin "P$34") (pinfunction "PB13_P$34") (pintype "bidirectional"))
    )
    (net (code "155") (name "unconnected-(CPU-PB14-PadP$35)") (class "Default")
      (node (ref "CPU") (pin "P$35") (pinfunction "PB14_P$35") (pintype "bidirectional"))
    )
    (net (code "156") (name "unconnected-(CPU-PB15-PadP$36)") (class "Default")
      (node (ref "CPU") (pin "P$36") (pinfunction "PB15_P$36") (pintype "bidirectional"))
    )
    (net (code "157") (name "unconnected-(CPU-PC0-PadP$8)") (class "Default")
      (node (ref "CPU") (pin "P$8") (pinfunction "PC0_P$8") (pintype "bidirectional"))
    )
    (net (code "158") (name "unconnected-(CPU-PC3-PadP$11)") (class "Default")
      (node (ref "CPU") (pin "P$11") (pinfunction "PC3_P$11") (pintype "bidirectional"))
    )
    (net (code "159") (name "unconnected-(CPU-PC4-PadP$24)") (class "Default")
      (node (ref "CPU") (pin "P$24") (pinfunction "PC4_P$24") (pintype "bidirectional"))
    )
    (net (code "160") (name "unconnected-(CPU-PC5-PadP$25)") (class "Default")
      (node (ref "CPU") (pin "P$25") (pinfunction "PC5_P$25") (pintype "bidirectional"))
    )
    (net (code "161") (name "unconnected-(CPU-PC6-PadP$37)") (class "Default")
      (node (ref "CPU") (pin "P$37") (pinfunction "PC6_P$37") (pintype "bidirectional"))
    )
    (net (code "162") (name "unconnected-(CPU-PC7-PadP$38)") (class "Default")
      (node (ref "CPU") (pin "P$38") (pinfunction "PC7_P$38") (pintype "bidirectional"))
    )
    (net (code "163") (name "unconnected-(CPU-PC11-PadP$52)") (class "Default")
      (node (ref "CPU") (pin "P$52") (pinfunction "PC11_P$52") (pintype "bidirectional"))
    )
    (net (code "164") (name "unconnected-(CPU-PC12-PadP$53)") (class "Default")
      (node (ref "CPU") (pin "P$53") (pinfunction "PC12_P$53") (pintype "bidirectional"))
    )
    (net (code "165") (name "unconnected-(CPU-PC13-PadP$2)") (class "Default")
      (node (ref "CPU") (pin "P$2") (pinfunction "PC13_P$2") (pintype "bidirectional"))
    )
    (net (code "166") (name "unconnected-(CPU-PC14-PadP$3)") (class "Default")
      (node (ref "CPU") (pin "P$3") (pinfunction "PC14_P$3") (pintype "bidirectional"))
    )
    (net (code "167") (name "unconnected-(CPU-PC15-PadP$4)") (class "Default")
      (node (ref "CPU") (pin "P$4") (pinfunction "PC15_P$4") (pintype "bidirectional"))
    )
    (net (code "168") (name "unconnected-(CPU-PD2-PadP$54)") (class "Default")
      (node (ref "CPU") (pin "P$54") (pinfunction "PD2_P$54") (pintype "bidirectional"))
    )
    (net (code "169") (name "unconnected-(J3-GND-Pad2)") (class "Default")
      (node (ref "J3") (pin "2") (pinfunction "GND_2") (pintype "passive"))
    )
    (net (code "170") (name "unconnected-(J3-GND-Pad3)") (class "Default")
      (node (ref "J3") (pin "3") (pinfunction "GND_3") (pintype "passive"))
    )
    (net (code "171") (name "unconnected-(J3-GND-Pad4)") (class "Default")
      (node (ref "J3") (pin "4") (pinfunction "GND_4") (pintype "passive"))
    )
    (net (code "172") (name "unconnected-(J4-GND-Pad2)") (class "Default")
      (node (ref "J4") (pin "2") (pinfunction "GND_2") (pintype "passive"))
    )
    (net (code "173") (name "unconnected-(J4-GND-Pad3)") (class "Default")
      (node (ref "J4") (pin "3") (pinfunction "GND_3") (pintype "passive"))
    )
    (net (code "174") (name "unconnected-(J4-GND-Pad4)") (class "Default")
      (node (ref "J4") (pin "4") (pinfunction "GND_4") (pintype "passive"))
    )
    (net (code "175") (name "unconnected-(J5-GND-Pad2)") (class "Default")
      (node (ref "J5") (pin "2") (pinfunction "GND_2") (pintype "passive"))
    )
    (net (code "176") (name "unconnected-(J5-GND-Pad3)") (class "Default")
      (node (ref "J5") (pin "3") (pinfunction "GND_3") (pintype "passive"))
    )
    (net (code "177") (name "unconnected-(J5-GND-Pad4)") (class "Default")
      (node (ref "J5") (pin "4") (pinfunction "GND_4") (pintype "passive"))
    )
    (net (code "178") (name "unconnected-(J6-Pad1)") (class "Default")
      (node (ref "J6") (pin "1") (pinfunction "1_1") (pintype "passive"))
    )
    (net (code "179") (name "unconnected-(J6-Pad17)") (class "Default")
      (node (ref "J6") (pin "17") (pinfunction "17_17") (pintype "passive"))
    )
    (net (code "180") (name "unconnected-(J6-Pad22)") (class "Default")
      (node (ref "J6") (pin "22") (pinfunction "22_22") (pintype "passive"))
    )
    (net (code "181") (name "unconnected-(J6-Pad29)") (class "Default")
      (node (ref "J6") (pin "29") (pinfunction "29_29") (pintype "passive"))
    )
    (net (code "182") (name "unconnected-(J6-Pad31)") (class "Default")
      (node (ref "J6") (pin "31") (pinfunction "31_31") (pintype "passive"))
    )
    (net (code "183") (name "unconnected-(J6-Pad32)") (class "Default")
      (node (ref "J6") (pin "32") (pinfunction "32_32") (pintype "passive"))
    )
    (net (code "184") (name "unconnected-(J6-Pad36)") (class "Default")
      (node (ref "J6") (pin "36") (pinfunction "36_36") (pintype "passive"))
    )
    (net (code "185") (name "unconnected-(J6-Pad38)") (class "Default")
      (node (ref "J6") (pin "38") (pinfunction "38_38") (pintype "passive"))
    )
    (net (code "186") (name "unconnected-(J6-Pad40)") (class "Default")
      (node (ref "J6") (pin "40") (pinfunction "40_40") (pintype "passive"))
    )
    (net (code "187") (name "unconnected-(PSU-PA9-PadP$42)") (class "Default")
      (node (ref "PSU") (pin "P$42") (pinfunction "PA9_P$42") (pintype "bidirectional"))
    )
    (net (code "188") (name "unconnected-(PSU-PA10-PadP$43)") (class "Default")
      (node (ref "PSU") (pin "P$43") (pinfunction "PA10_P$43") (pintype "bidirectional"))
    )
    (net (code "189") (name "unconnected-(PSU-PA11-PadP$44)") (class "Default")
      (node (ref "PSU") (pin "P$44") (pinfunction "PA11_P$44") (pintype "bidirectional"))
    )
    (net (code "190") (name "unconnected-(PSU-PA12-PadP$45)") (class "Default")
      (node (ref "PSU") (pin "P$45") (pinfunction "PA12_P$45") (pintype "bidirectional"))
    )
    (net (code "191") (name "unconnected-(PSU-PB0-PadP$26)") (class "Default")
      (node (ref "PSU") (pin "P$26") (pinfunction "PB0_P$26") (pintype "bidirectional"))
    )
    (net (code "192") (name "unconnected-(PSU-PB1-PadP$27)") (class "Default")
      (node (ref "PSU") (pin "P$27") (pinfunction "PB1_P$27") (pintype "bidirectional"))
    )
    (net (code "193") (name "unconnected-(PSU-PB2-PadP$28)") (class "Default")
      (node (ref "PSU") (pin "P$28") (pinfunction "PB2_P$28") (pintype "bidirectional"))
    )
    (net (code "194") (name "unconnected-(PSU-PB5-PadP$57)") (class "Default")
      (node (ref "PSU") (pin "P$57") (pinfunction "PB5_P$57") (pintype "bidirectional"))
    )
    (net (code "195") (name "unconnected-(PSU-PB6-PadP$58)") (class "Default")
      (node (ref "PSU") (pin "P$58") (pinfunction "PB6_P$58") (pintype "bidirectional"))
    )
    (net (code "196") (name "unconnected-(PSU-PB7-PadP$59)") (class "Default")
      (node (ref "PSU") (pin "P$59") (pinfunction "PB7_P$59") (pintype "bidirectional"))
    )
    (net (code "197") (name "unconnected-(PSU-PB8-PadP$61)") (class "Default")
      (node (ref "PSU") (pin "P$61") (pinfunction "PB8_P$61") (pintype "bidirectional"))
    )
    (net (code "198") (name "unconnected-(PSU-PB9-PadP$62)") (class "Default")
      (node (ref "PSU") (pin "P$62") (pinfunction "PB9_P$62") (pintype "bidirectional"))
    )
    (net (code "199") (name "unconnected-(PSU-PB10-PadP$29)") (class "Default")
      (node (ref "PSU") (pin "P$29") (pinfunction "PB10_P$29") (pintype "bidirectional"))
    )
    (net (code "200") (name "unconnected-(PSU-PB12-PadP$33)") (class "Default")
      (node (ref "PSU") (pin "P$33") (pinfunction "PB12_P$33") (pintype "bidirectional"))
    )
    (net (code "201") (name "unconnected-(PSU-PB13-PadP$34)") (class "Default")
      (node (ref "PSU") (pin "P$34") (pinfunction "PB13_P$34") (pintype "bidirectional"))
    )
    (net (code "202") (name "unconnected-(PSU-PB14-PadP$35)") (class "Default")
      (node (ref "PSU") (pin "P$35") (pinfunction "PB14_P$35") (pintype "bidirectional"))
    )
    (net (code "203") (name "unconnected-(PSU-PB15-PadP$36)") (class "Default")
      (node (ref "PSU") (pin "P$36") (pinfunction "PB15_P$36") (pintype "bidirectional"))
    )
    (net (code "204") (name "unconnected-(PSU-PC3-PadP$11)") (class "Default")
      (node (ref "PSU") (pin "P$11") (pinfunction "PC3_P$11") (pintype "bidirectional"))
    )
    (net (code "205") (name "unconnected-(PSU-PC4-PadP$24)") (class "Default")
      (node (ref "PSU") (pin "P$24") (pinfunction "PC4_P$24") (pintype "bidirectional"))
    )
    (net (code "206") (name "unconnected-(PSU-PC5-PadP$25)") (class "Default")
      (node (ref "PSU") (pin "P$25") (pinfunction "PC5_P$25") (pintype "bidirectional"))
    )
    (net (code "207") (name "unconnected-(PSU-PC6-PadP$37)") (class "Default")
      (node (ref "PSU") (pin "P$37") (pinfunction "PC6_P$37") (pintype "bidirectional"))
    )
    (net (code "208") (name "unconnected-(PSU-PC7-PadP$38)") (class "Default")
      (node (ref "PSU") (pin "P$38") (pinfunction "PC7_P$38") (pintype "bidirectional"))
    )
    (net (code "209") (name "unconnected-(PSU-PC8-PadP$39)") (class "Default")
      (node (ref "PSU") (pin "P$39") (pinfunction "PC8_P$39") (pintype "bidirectional"))
    )
    (net (code "210") (name "unconnected-(PSU-PC9-PadP$40)") (class "Default")
      (node (ref "PSU") (pin "P$40") (pinfunction "PC9_P$40") (pintype "bidirectional"))
    )
    (net (code "211") (name "unconnected-(PSU-PC10-PadP$51)") (class "Default")
      (node (ref "PSU") (pin "P$51") (pinfunction "PC10_P$51") (pintype "bidirectional"))
    )
    (net (code "212") (name "unconnected-(PSU-PC11-PadP$52)") (class "Default")
      (node (ref "PSU") (pin "P$52") (pinfunction "PC11_P$52") (pintype "bidirectional"))
    )
    (net (code "213") (name "unconnected-(PSU-PC12-PadP$53)") (class "Default")
      (node (ref "PSU") (pin "P$53") (pinfunction "PC12_P$53") (pintype "bidirectional"))
    )
    (net (code "214") (name "unconnected-(PSU-PC13-PadP$2)") (class "Default")
      (node (ref "PSU") (pin "P$2") (pinfunction "PC13_P$2") (pintype "bidirectional"))
    )
    (net (code "215") (name "unconnected-(PSU-PC14-PadP$3)") (class "Default")
      (node (ref "PSU") (pin "P$3") (pinfunction "PC14_P$3") (pintype "bidirectional"))
    )
    (net (code "216") (name "unconnected-(PSU-PC15-PadP$4)") (class "Default")
      (node (ref "PSU") (pin "P$4") (pinfunction "PC15_P$4") (pintype "bidirectional"))
    )
    (net (code "217") (name "unconnected-(PSU-PD2-PadP$54)") (class "Default")
      (node (ref "PSU") (pin "P$54") (pinfunction "PD2_P$54") (pintype "bidirectional"))
    )
    (net (code "218") (name "unconnected-(PSU-PH0_XI-PadP$5)") (class "Default")
      (node (ref "PSU") (pin "P$5") (pinfunction "PH0_XI_P$5") (pintype "bidirectional"))
    )
    (net (code "219") (name "unconnected-(PSU-PH1_XO-PadP$6)") (class "Default")
      (node (ref "PSU") (pin "P$6") (pinfunction "PH1_XO_P$6") (pintype "bidirectional"))
    )
    (net (code "220") (name "unconnected-(U1-ANTON-Pad13)") (class "Default")
      (node (ref "U1") (pin "13") (pinfunction "ANTON_13") (pintype "output"))
    )
    (net (code "221") (name "unconnected-(U1-FORCE_ON-Pad18)") (class "Default")
      (node (ref "U1") (pin "18") (pinfunction "FORCE_ON_18") (pintype "bidirectional"))
    )
    (net (code "222") (name "unconnected-(U1-RESERVED-Pad16)") (class "Default")
      (node (ref "U1") (pin "16") (pinfunction "RESERVED_16") (pintype "passive"))
    )
    (net (code "223") (name "unconnected-(U1-RESERVED-Pad17)") (class "Default")
      (node (ref "U1") (pin "17") (pinfunction "RESERVED_17") (pintype "passive"))
    )
    (net (code "224") (name "unconnected-(U1-STANDBY-Pad5)") (class "Default")
      (node (ref "U1") (pin "5") (pinfunction "STANDBY_5") (pintype "bidirectional"))
    )
    (net (code "225") (name "unconnected-(USB1-DM-Pad2)") (class "Default")
      (node (ref "USB1") (pin "2") (pinfunction "DM_2") (pintype "bidirectional"))
    )
    (net (code "226") (name "unconnected-(USB1-DP-Pad3)") (class "Default")
      (node (ref "USB1") (pin "3") (pinfunction "DP_3") (pintype "bidirectional"))
    )
    (net (code "227") (name "unconnected-(USB1-ID-Pad4)") (class "Default")
      (node (ref "USB1") (pin "4") (pinfunction "ID_4") (pintype "bidirectional"))
    )
  )
)
